# Main.net
KiCad netlist of a schematic drawn in EAGLE
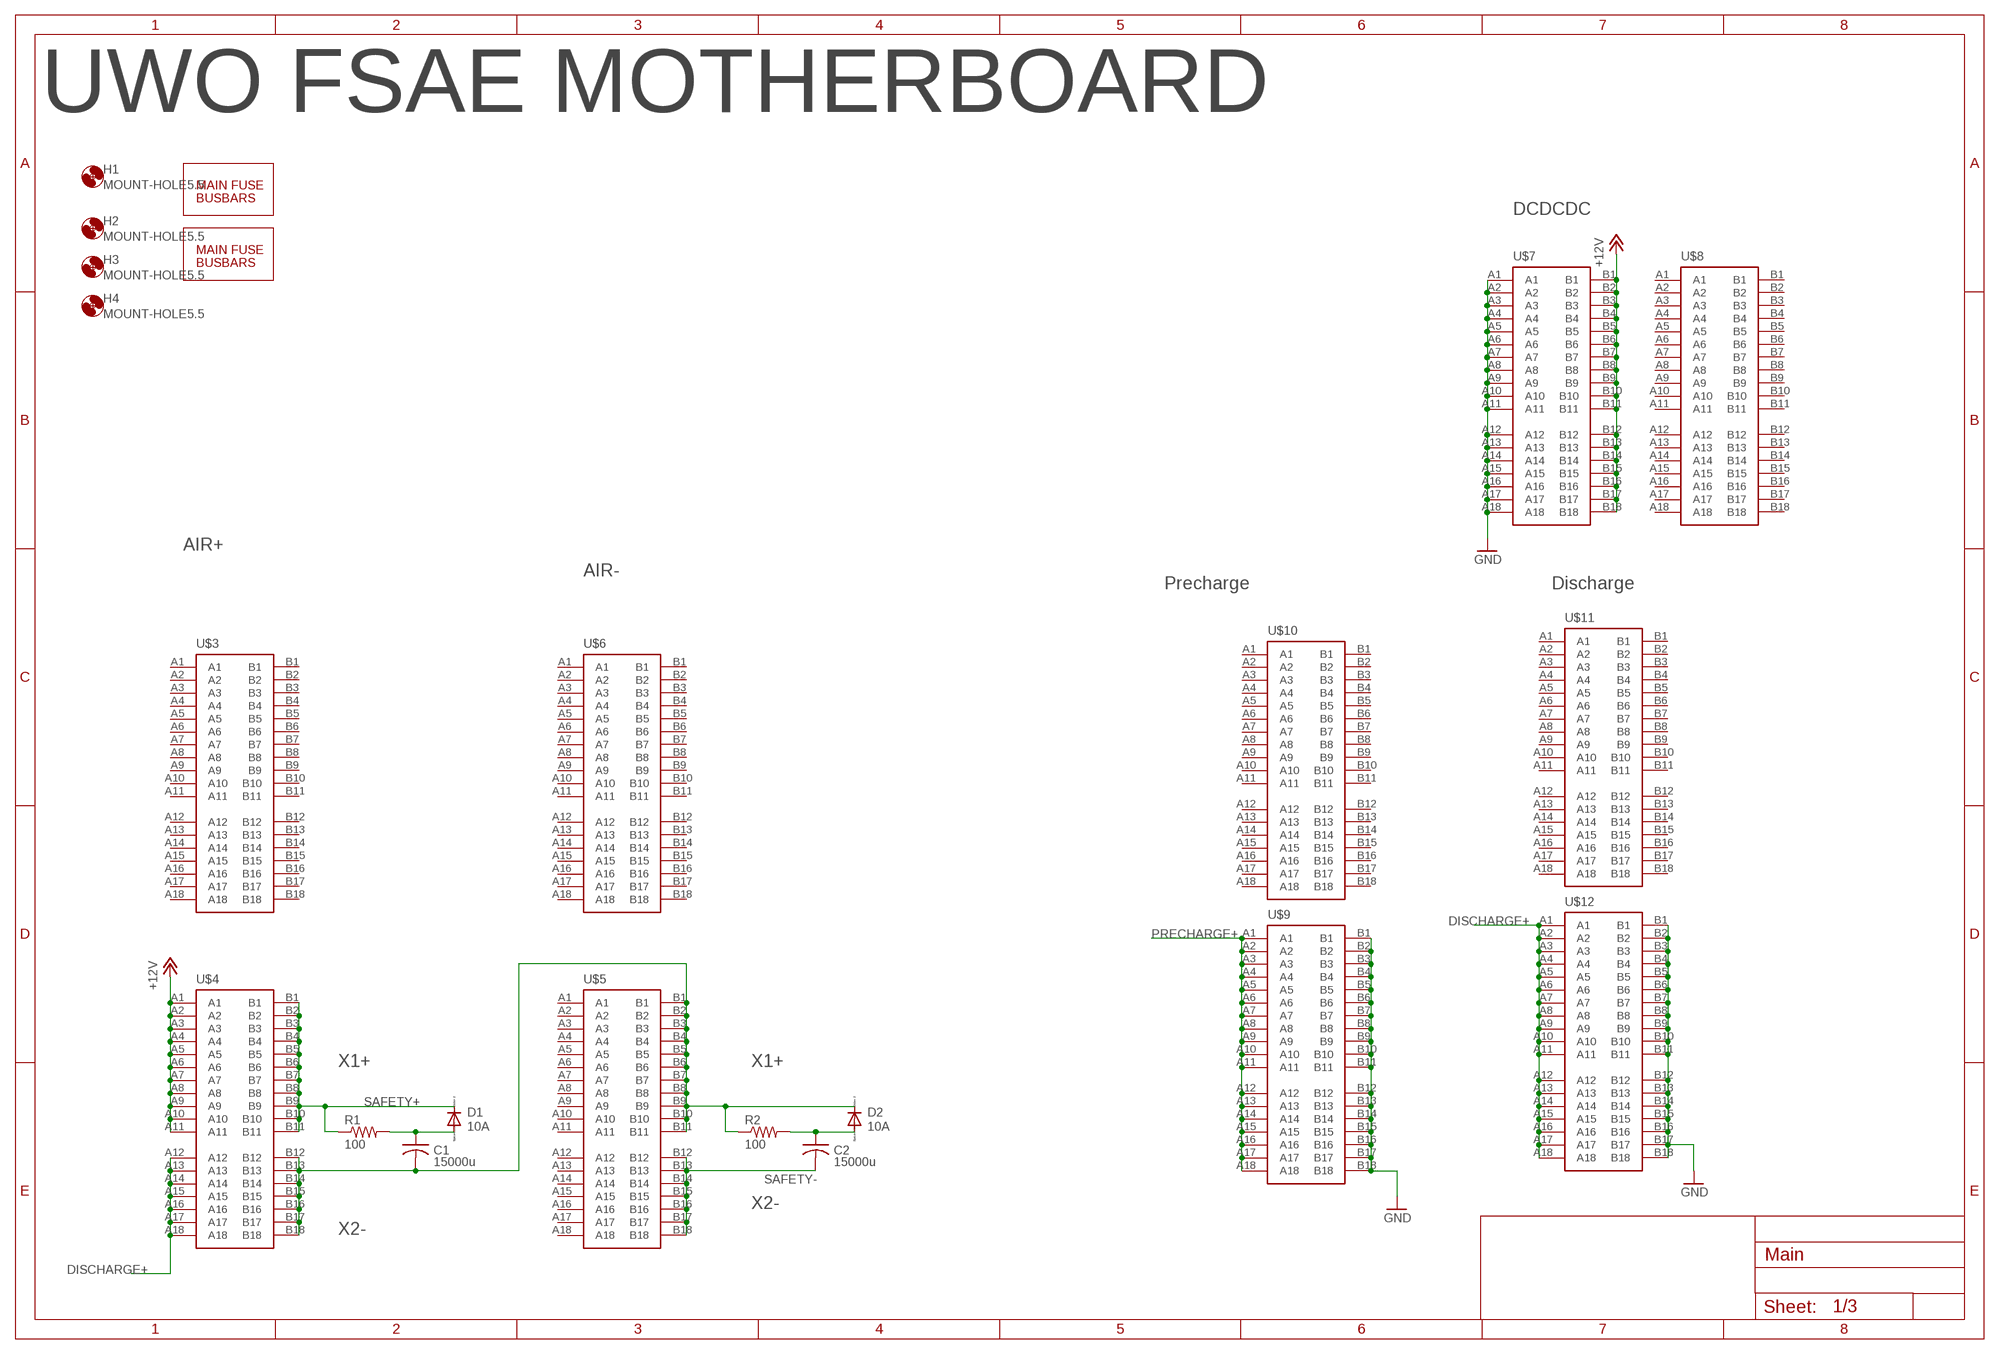
[diagram p0: schematic, sheet 1]
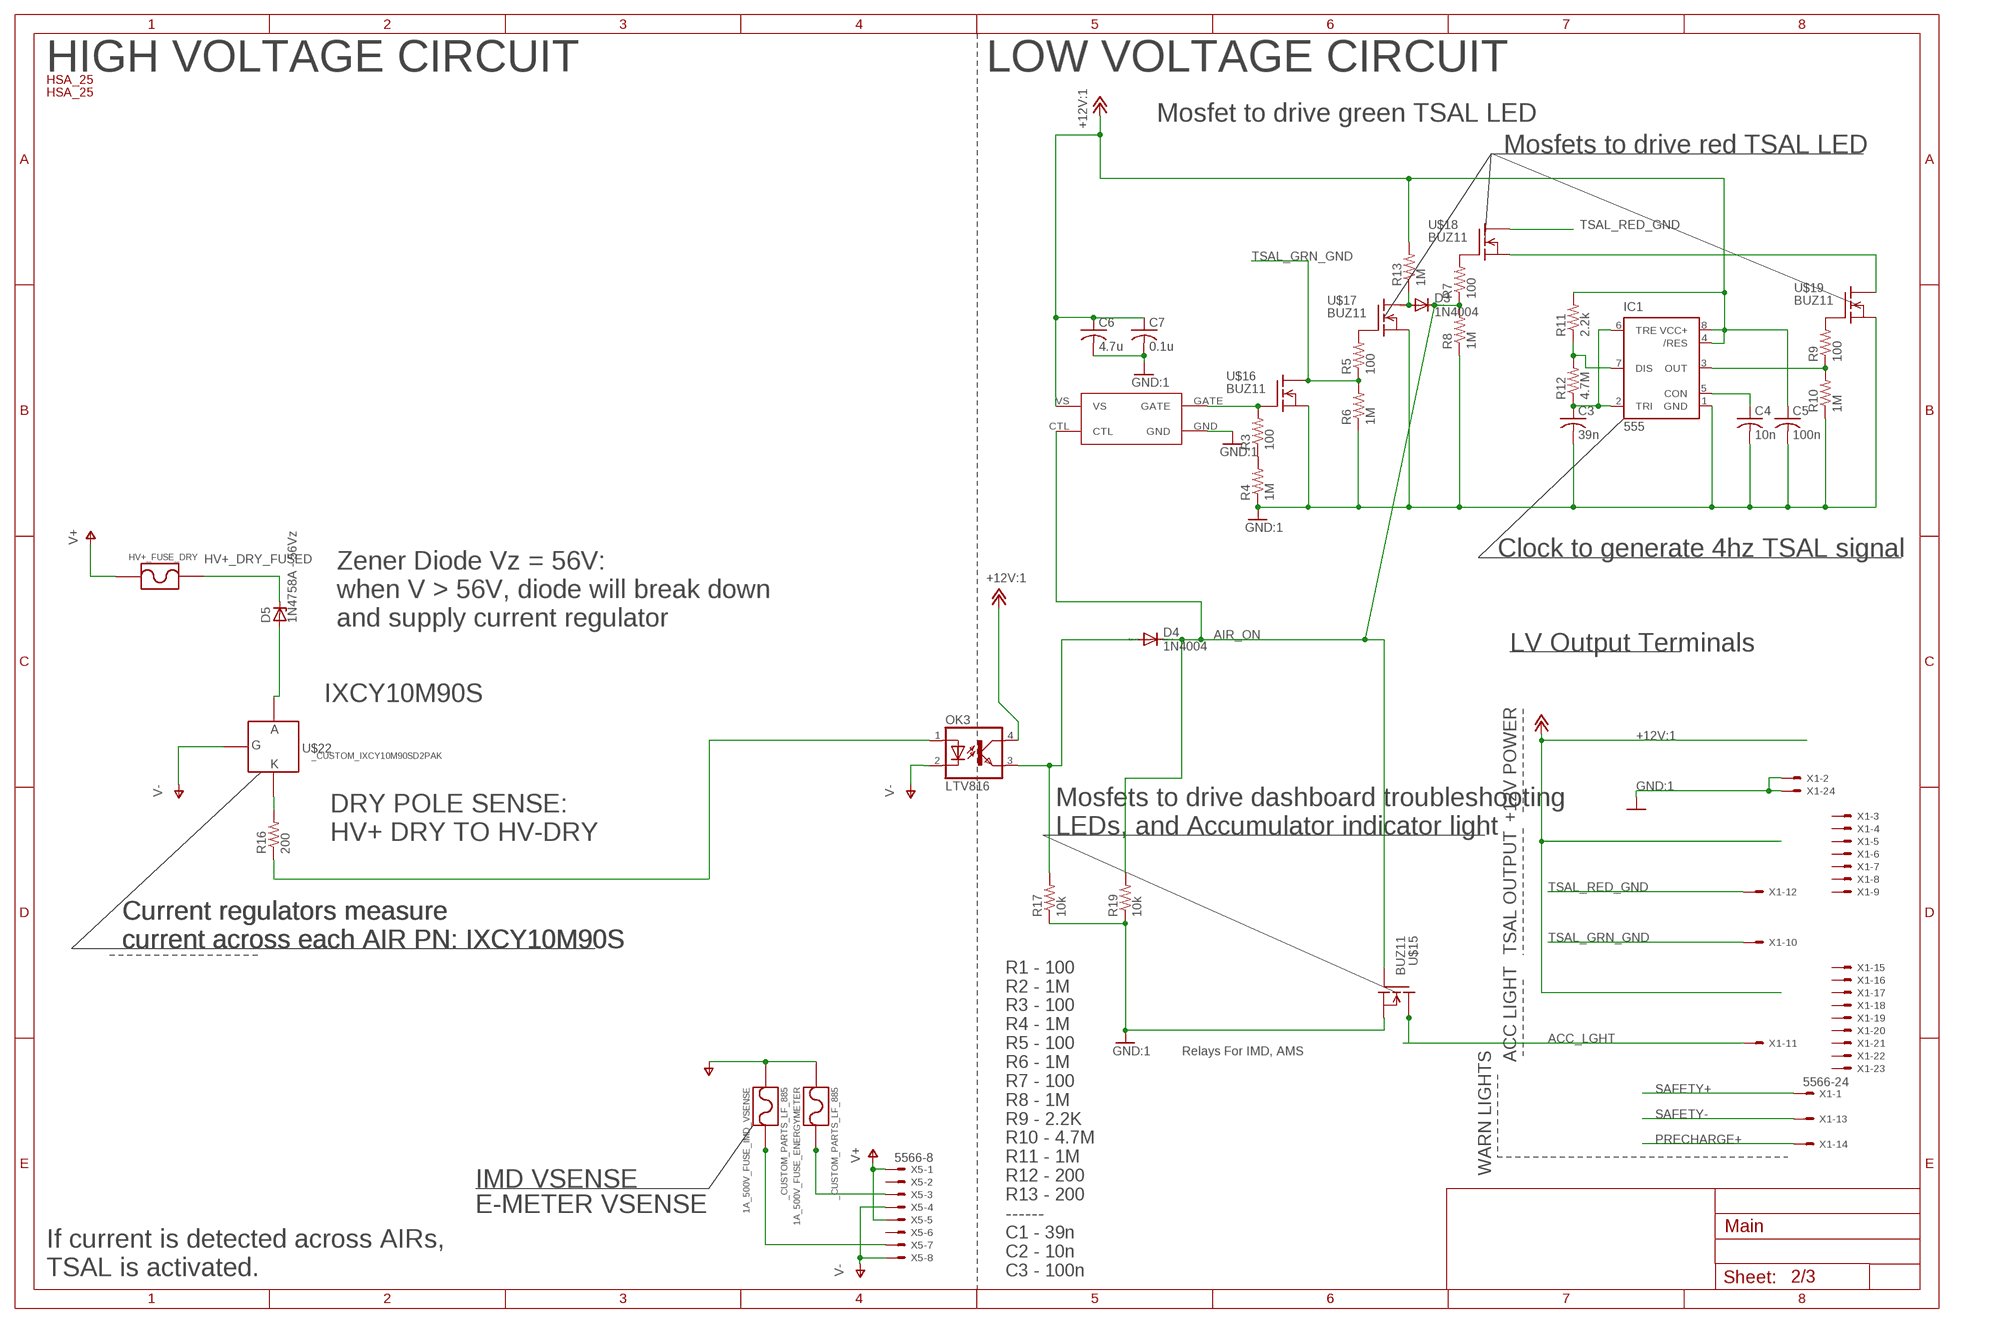
[diagram p1: schematic, sheet 2]
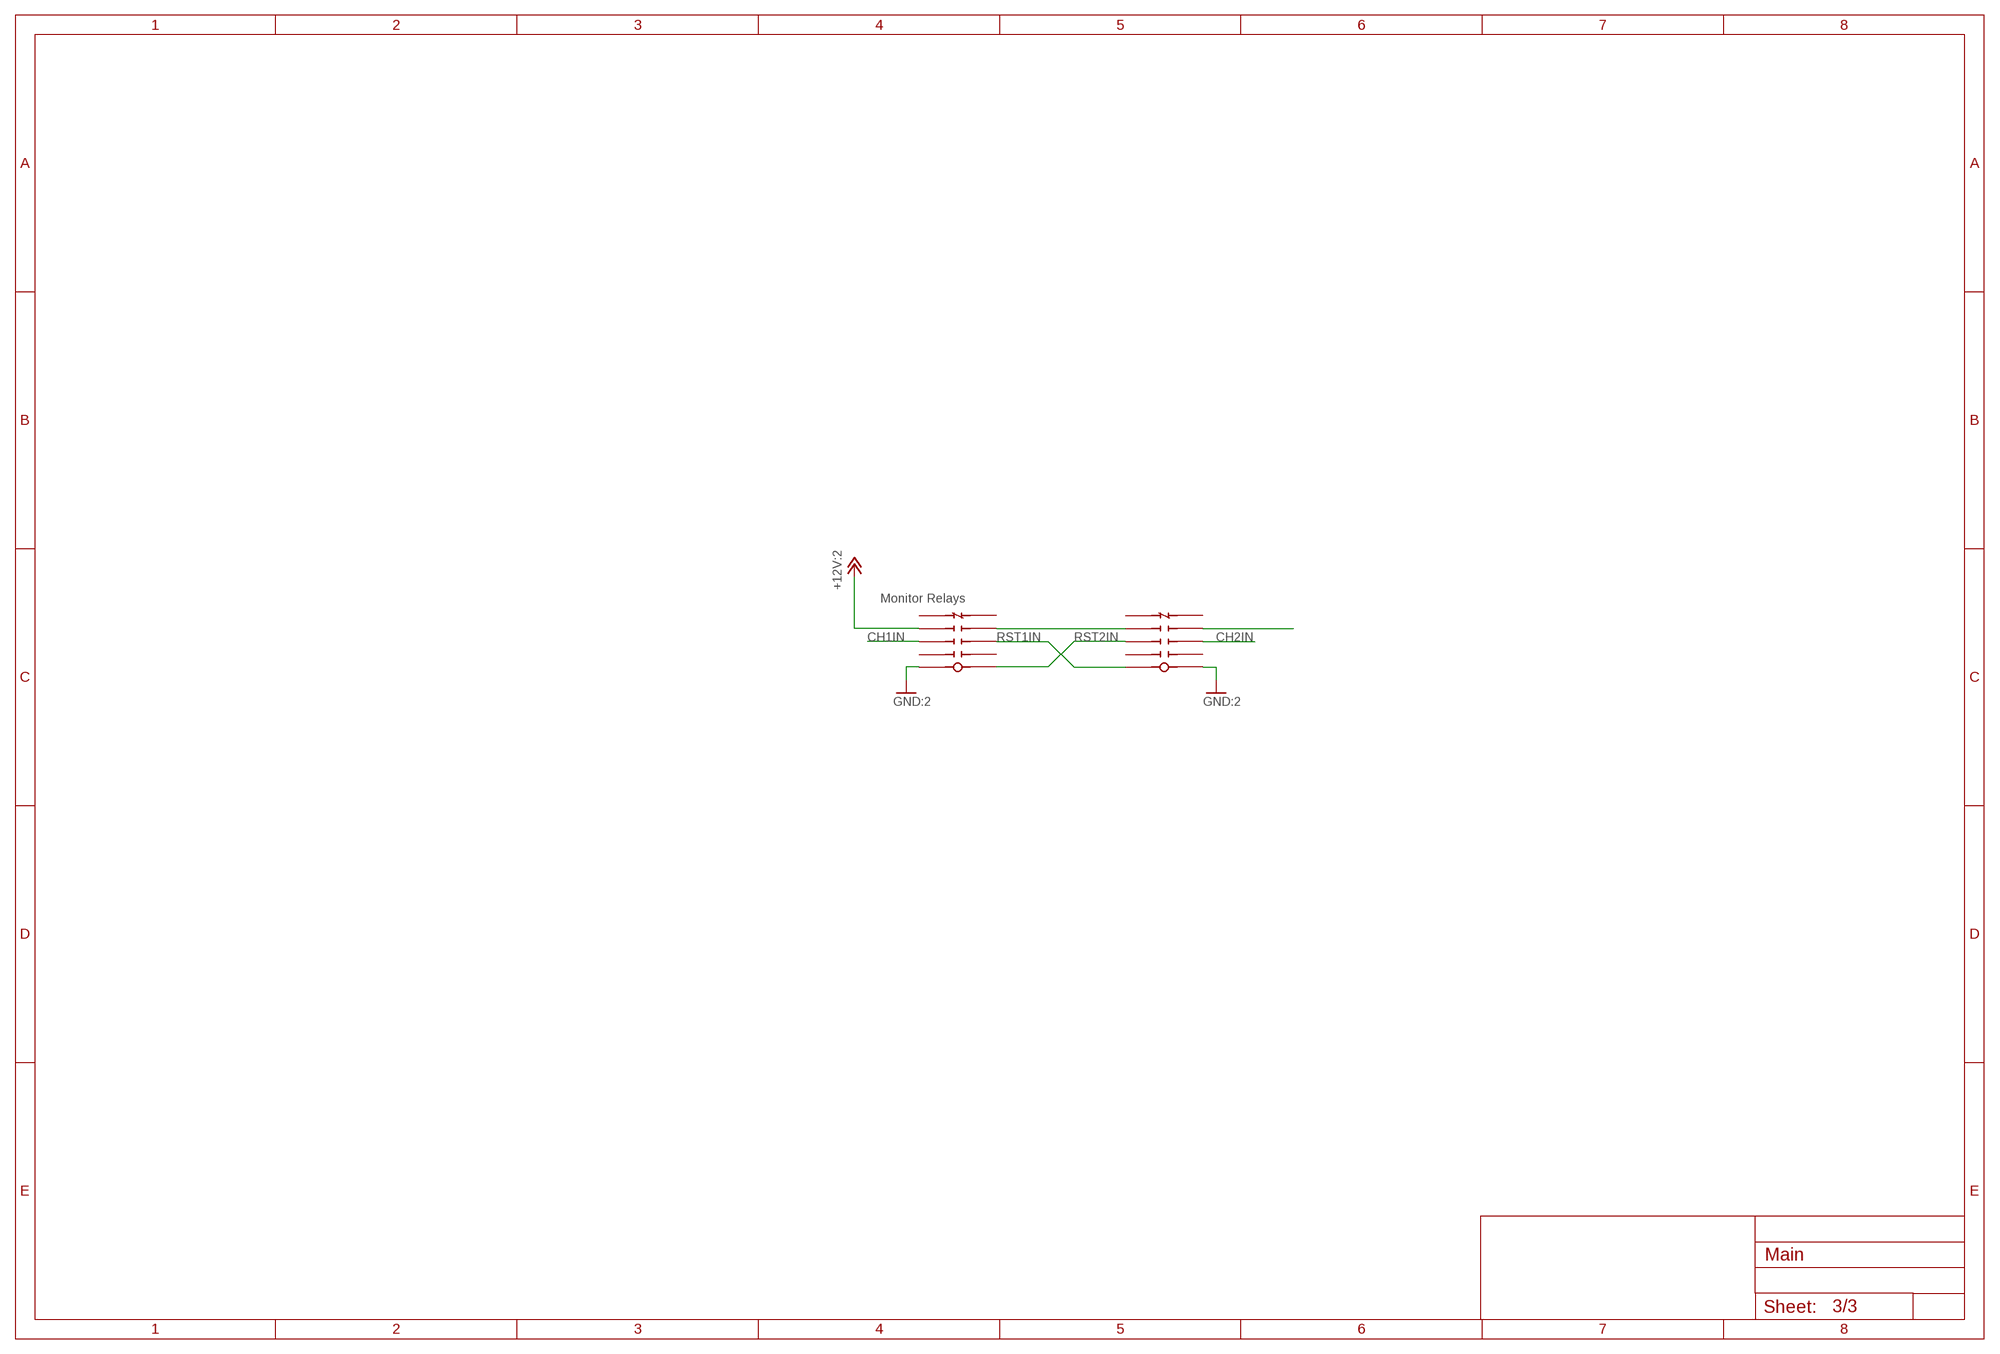
[diagram p2: schematic, sheet 3]

(export (version "E")
  (design (tool "Eeschema 10.0.6"))
  (components
    (comp (ref "1A_500V_FUSE_ENERGYMETER")
      (value "_CUSTOM_PARTS_LF_885")
      (footprint "eagle-import:_CUSTOM_PARTS_LF_885")
      (libsource (lib "eagle-import") (part "_CUSTOM_PARTS_LF_885"))
    )
    (comp (ref "1A_500V_FUSE_IMD_VSENSE")
      (value "_CUSTOM_PARTS_LF_885")
      (footprint "eagle-import:_CUSTOM_PARTS_LF_885")
      (libsource (lib "eagle-import") (part "_CUSTOM_PARTS_LF_885"))
    )
    (comp (ref "C3")
      (value "39n")
      (footprint "eagle-import:C0805")
      (libsource (lib "eagle-import") (part "C-USC0805"))
    )
    (comp (ref "C4")
      (value "10n")
      (footprint "eagle-import:C0805")
      (libsource (lib "eagle-import") (part "C-USC0805"))
    )
    (comp (ref "C5")
      (value "100n")
      (footprint "eagle-import:C0805")
      (libsource (lib "eagle-import") (part "C-USC0805"))
    )
    (comp (ref "C6")
      (value "4.7u")
      (footprint "eagle-import:C0805")
      (libsource (lib "eagle-import") (part "C-USC0805"))
    )
    (comp (ref "C7")
      (value "0.1u")
      (footprint "eagle-import:C0805")
      (libsource (lib "eagle-import") (part "C-USC0805"))
    )
    (comp (ref "D3")
      (value "1N4004")
      (footprint "eagle-import:DO41-10")
      (libsource (lib "eagle-import") (part "1N4004"))
    )
    (comp (ref "D4")
      (value "1N4004")
      (footprint "eagle-import:DO41-10")
      (libsource (lib "eagle-import") (part "1N4004"))
    )
    (comp (ref "D5")
      (value "1N4758A - 56Vz")
      (footprint "eagle-import:ZDIO12.5")
      (libsource (lib "eagle-import") (part "ZENER-DIODEZD-12.5"))
    )
    (comp (ref "HV+_FUSE_DRY")
      (value "_CUSTOM_PARTS_LF_885")
      (footprint "eagle-import:_CUSTOM_PARTS_LF_885")
      (libsource (lib "eagle-import") (part "_CUSTOM_PARTS_LF_885"))
    )
    (comp (ref "IC1")
      (value "555")
      (footprint "eagle-import:DIP08")
      (libsource (lib "eagle-import") (part "555P"))
    )
    (comp (ref "OK3")
      (value "LTV816")
      (footprint "eagle-import:DIL04")
      (libsource (lib "eagle-import") (part "LTV816"))
    )
    (comp (ref "R3")
      (value "100")
      (footprint "eagle-import:R0805_1")
      (libsource (lib "eagle-import") (part "R-US_?{colon}1R0805"))
    )
    (comp (ref "R4")
      (value "1M")
      (footprint "eagle-import:R0805_1")
      (libsource (lib "eagle-import") (part "R-US_?{colon}1R0805"))
    )
    (comp (ref "R5")
      (value "100")
      (footprint "eagle-import:R0805_1")
      (libsource (lib "eagle-import") (part "R-US_?{colon}1R0805"))
    )
    (comp (ref "R6")
      (value "1M")
      (footprint "eagle-import:R0805_1")
      (libsource (lib "eagle-import") (part "R-US_?{colon}1R0805"))
    )
    (comp (ref "R7")
      (value "100")
      (footprint "eagle-import:R0805_1")
      (libsource (lib "eagle-import") (part "R-US_?{colon}1R0805"))
    )
    (comp (ref "R8")
      (value "1M")
      (footprint "eagle-import:R0805_1")
      (libsource (lib "eagle-import") (part "R-US_?{colon}1R0805"))
    )
    (comp (ref "R9")
      (value "100")
      (footprint "eagle-import:R0805_1")
      (libsource (lib "eagle-import") (part "R-US_?{colon}1R0805"))
    )
    (comp (ref "R10")
      (value "1M")
      (footprint "eagle-import:R0805_1")
      (libsource (lib "eagle-import") (part "R-US_?{colon}1R0805"))
    )
    (comp (ref "R11")
      (value "2.2k")
      (footprint "eagle-import:R0805_1")
      (libsource (lib "eagle-import") (part "R-US_?{colon}1R0805"))
    )
    (comp (ref "R12")
      (value "4.7M")
      (footprint "eagle-import:R0805_1")
      (libsource (lib "eagle-import") (part "R-US_?{colon}1R0805"))
    )
    (comp (ref "R13")
      (value "1M")
      (footprint "eagle-import:R0805_1")
      (libsource (lib "eagle-import") (part "R-US_?{colon}1R0805"))
    )
    (comp (ref "R16")
      (value "200")
      (footprint "eagle-import:R2010")
      (libsource (lib "eagle-import") (part "R-US_R2010"))
    )
    (comp (ref "R17")
      (value "10k")
      (footprint "eagle-import:R0805_1")
      (libsource (lib "eagle-import") (part "R-US_?{colon}1R0805"))
    )
    (comp (ref "R19")
      (value "10k")
      (footprint "eagle-import:R0805_1")
      (libsource (lib "eagle-import") (part "R-US_?{colon}1R0805"))
    )
    (comp (ref "U$15")
      (value "BUZ11")
      (footprint "eagle-import:TO220")
      (libsource (lib "eagle-import") (part "BUZ11"))
    )
    (comp (ref "U$16")
      (value "BUZ11")
      (footprint "eagle-import:TO220")
      (libsource (lib "eagle-import") (part "BUZ11"))
    )
    (comp (ref "U$17")
      (value "BUZ11")
      (footprint "eagle-import:TO220")
      (libsource (lib "eagle-import") (part "BUZ11"))
    )
    (comp (ref "U$18")
      (value "BUZ11")
      (footprint "eagle-import:TO220")
      (libsource (lib "eagle-import") (part "BUZ11"))
    )
    (comp (ref "U$19")
      (value "BUZ11")
      (footprint "eagle-import:TO220")
      (libsource (lib "eagle-import") (part "BUZ11"))
    )
    (comp (ref "U$22")
      (value "_CUSTOM_IXCY10M90SD2PAK")
      (footprint "eagle-import:TO228P991X238-3")
      (libsource (lib "eagle-import") (part "_CUSTOM_IXCY10M90SD2PAK"))
    )
    (comp (ref "U$23")
      (value "MIC4417")
      (footprint "eagle-import:PDM_2019_REVB_MIC4416YM4-TR")
      (libsource (lib "eagle-import") (part "MIC4417"))
    )
    (comp (ref "U$24")
      (value "HSA25")
      (footprint "eagle-import:HSA_25_FOOT")
      (libsource (lib "eagle-import") (part "HSA25"))
    )
    (comp (ref "U$25")
      (value "HSA25")
      (footprint "eagle-import:HSA_25_FOOT")
      (libsource (lib "eagle-import") (part "HSA25"))
    )
    (comp (ref "X1")
      (value "5566-24")
      (footprint "eagle-import:5566-24")
      (fields (field (name "MF") "MOLEX"))
      (libsource (lib "eagle-import") (part "5566-24"))
    )
    (comp (ref "X5")
      (value "5566-8")
      (footprint "eagle-import:5566-8")
      (fields (field (name "MF") "MOLEX"))
      (libsource (lib "eagle-import") (part "5566-8"))
    )
    (comp (ref "C1")
      (value "15000u")
      (footprint "eagle-import:CAPPRD750W65D1800H3700B")
      (libsource (lib "eagle-import") (part "AIR_HOLDUP_CAP"))
    )
    (comp (ref "C2")
      (value "15000u")
      (footprint "eagle-import:CAPPRD750W65D1800H3700B")
      (libsource (lib "eagle-import") (part "AIR_HOLDUP_CAP"))
    )
    (comp (ref "D1")
      (value "10A")
      (footprint "eagle-import:DIOAD1570W120L850D500B")
      (libsource (lib "eagle-import") (part "AIR_HOLDUP_DIODE"))
    )
    (comp (ref "D2")
      (value "10A")
      (footprint "eagle-import:DIOAD1570W120L850D500B")
      (libsource (lib "eagle-import") (part "AIR_HOLDUP_DIODE"))
    )
    (comp (ref "H1")
      (value "MOUNT-HOLE5.5")
      (footprint "eagle-import:5,5")
      (libsource (lib "eagle-import") (part "MOUNT-HOLE5.5"))
    )
    (comp (ref "H2")
      (value "MOUNT-HOLE5.5")
      (footprint "eagle-import:5,5")
      (libsource (lib "eagle-import") (part "MOUNT-HOLE5.5"))
    )
    (comp (ref "H3")
      (value "MOUNT-HOLE5.5")
      (footprint "eagle-import:5,5")
      (libsource (lib "eagle-import") (part "MOUNT-HOLE5.5"))
    )
    (comp (ref "H4")
      (value "MOUNT-HOLE5.5")
      (footprint "eagle-import:5,5")
      (libsource (lib "eagle-import") (part "MOUNT-HOLE5.5"))
    )
    (comp (ref "R1")
      (value "100")
      (footprint "eagle-import:RESAD976W63L650D250B")
      (libsource (lib "eagle-import") (part "AIR_HOLDUP_RESISTOR"))
    )
    (comp (ref "R2")
      (value "100")
      (footprint "eagle-import:RESAD976W63L650D250B")
      (libsource (lib "eagle-import") (part "AIR_HOLDUP_RESISTOR"))
    )
    (comp (ref "U$1")
      (value "FUSE_HOLDER")
      (footprint "eagle-import:FUSE_HOLDER")
      (libsource (lib "eagle-import") (part "FUSE_HOLDER"))
    )
    (comp (ref "U$2")
      (value "FUSE_HOLDER")
      (footprint "eagle-import:FUSE_HOLDER")
      (libsource (lib "eagle-import") (part "FUSE_HOLDER"))
    )
    (comp (ref "U$3")
      (value "PCIE-36-CONN")
      (footprint "eagle-import:PCI-E-36-CONN")
      (libsource (lib "eagle-import") (part "PCIE-36-CONN"))
    )
    (comp (ref "U$4")
      (value "PCIE-36-CONN")
      (footprint "eagle-import:PCI-E-36-CONN")
      (libsource (lib "eagle-import") (part "PCIE-36-CONN"))
    )
    (comp (ref "U$5")
      (value "PCIE-36-CONN")
      (footprint "eagle-import:PCI-E-36-CONN")
      (libsource (lib "eagle-import") (part "PCIE-36-CONN"))
    )
    (comp (ref "U$6")
      (value "PCIE-36-CONN")
      (footprint "eagle-import:PCI-E-36-CONN")
      (libsource (lib "eagle-import") (part "PCIE-36-CONN"))
    )
    (comp (ref "U$7")
      (value "PCIE-36-CONN")
      (footprint "eagle-import:PCI-E-36-CONN")
      (libsource (lib "eagle-import") (part "PCIE-36-CONN"))
    )
    (comp (ref "U$8")
      (value "PCIE-36-CONN")
      (footprint "eagle-import:PCI-E-36-CONN")
      (libsource (lib "eagle-import") (part "PCIE-36-CONN"))
    )
    (comp (ref "U$9")
      (value "PCIE-36-CONN")
      (footprint "eagle-import:PCI-E-36-CONN")
      (libsource (lib "eagle-import") (part "PCIE-36-CONN"))
    )
    (comp (ref "U$10")
      (value "PCIE-36-CONN")
      (footprint "eagle-import:PCI-E-36-CONN")
      (libsource (lib "eagle-import") (part "PCIE-36-CONN"))
    )
    (comp (ref "U$11")
      (value "PCIE-36-CONN")
      (footprint "eagle-import:PCI-E-36-CONN")
      (libsource (lib "eagle-import") (part "PCIE-36-CONN"))
    )
    (comp (ref "U$12")
      (value "PCIE-36-CONN")
      (footprint "eagle-import:PCI-E-36-CONN")
      (libsource (lib "eagle-import") (part "PCIE-36-CONN"))
    )
    (comp (ref "U$13")
      (value "SR4M4012_TE")
      (footprint "eagle-import:SR4M4012_FOOT")
      (libsource (lib "eagle-import") (part "SR4M4012_TE"))
    )
    (comp (ref "U$14")
      (value "SR4M4012_TE")
      (footprint "eagle-import:SR4M4012_FOOT")
      (libsource (lib "eagle-import") (part "SR4M4012_TE"))
    )
  )
  (nets
    (net (code "1") (name "+12V") (class "Default")
      (node (ref "C5") (pin "1") (pinfunction "1_1") (pintype "passive"))
      (node (ref "C6") (pin "1") (pinfunction "1_1") (pintype "passive"))
      (node (ref "C7") (pin "1") (pinfunction "1_1") (pintype "passive"))
      (node (ref "IC1") (pin "4") (pinfunction "/RES_4") (pintype "input"))
      (node (ref "IC1") (pin "8") (pinfunction "VCC+_8") (pintype "power_in"))
      (node (ref "OK3") (pin "4") (pinfunction "COL_4") (pintype "passive"))
      (node (ref "R11") (pin "2") (pinfunction "2_2") (pintype "passive"))
      (node (ref "R13") (pin "2") (pinfunction "2_2") (pintype "passive"))
      (node (ref "U$13") (pin "NOA3") (pinfunction "NOA3_NOA3") (pintype "bidirectional"))
      (node (ref "U$23") (pin "VS") (pinfunction "VS_VS") (pintype "bidirectional"))
      (node (ref "U$4") (pin "A1") (pinfunction "A1_A1") (pintype "passive"))
      (node (ref "U$4") (pin "A10") (pinfunction "A10_A10") (pintype "passive"))
      (node (ref "U$4") (pin "A11") (pinfunction "A11_A11") (pintype "passive"))
      (node (ref "U$4") (pin "A2") (pinfunction "A2_A2") (pintype "passive"))
      (node (ref "U$4") (pin "A3") (pinfunction "A3_A3") (pintype "passive"))
      (node (ref "U$4") (pin "A4") (pinfunction "A4_A4") (pintype "passive"))
      (node (ref "U$4") (pin "A5") (pinfunction "A5_A5") (pintype "passive"))
      (node (ref "U$4") (pin "A6") (pinfunction "A6_A6") (pintype "passive"))
      (node (ref "U$4") (pin "A7") (pinfunction "A7_A7") (pintype "passive"))
      (node (ref "U$4") (pin "A8") (pinfunction "A8_A8") (pintype "passive"))
      (node (ref "U$4") (pin "A9") (pinfunction "A9_A9") (pintype "passive"))
      (node (ref "U$7") (pin "B1") (pinfunction "B1_B1") (pintype "passive"))
      (node (ref "U$7") (pin "B10") (pinfunction "B10_B10") (pintype "passive"))
      (node (ref "U$7") (pin "B11") (pinfunction "B11_B11") (pintype "passive"))
      (node (ref "U$7") (pin "B12") (pinfunction "B12_B12") (pintype "passive"))
      (node (ref "U$7") (pin "B13") (pinfunction "B13_B13") (pintype "passive"))
      (node (ref "U$7") (pin "B14") (pinfunction "B14_B14") (pintype "passive"))
      (node (ref "U$7") (pin "B15") (pinfunction "B15_B15") (pintype "passive"))
      (node (ref "U$7") (pin "B16") (pinfunction "B16_B16") (pintype "passive"))
      (node (ref "U$7") (pin "B17") (pinfunction "B17_B17") (pintype "passive"))
      (node (ref "U$7") (pin "B18") (pinfunction "B18_B18") (pintype "passive"))
      (node (ref "U$7") (pin "B2") (pinfunction "B2_B2") (pintype "passive"))
      (node (ref "U$7") (pin "B3") (pinfunction "B3_B3") (pintype "passive"))
      (node (ref "U$7") (pin "B4") (pinfunction "B4_B4") (pintype "passive"))
      (node (ref "U$7") (pin "B5") (pinfunction "B5_B5") (pintype "passive"))
      (node (ref "U$7") (pin "B6") (pinfunction "B6_B6") (pintype "passive"))
      (node (ref "U$7") (pin "B7") (pinfunction "B7_B7") (pintype "passive"))
      (node (ref "U$7") (pin "B8") (pinfunction "B8_B8") (pintype "passive"))
      (node (ref "U$7") (pin "B9") (pinfunction "B9_B9") (pintype "passive"))
    )
    (net (code "2") (name "ACC_LGHT") (class "Default")
      (node (ref "U$15") (pin "2") (pinfunction "D_2") (pintype "passive"))
      (node (ref "X1") (pin "11") (pinfunction "S_11") (pintype "passive"))
    )
    (net (code "3") (name "AIR_ON") (class "Default")
      (node (ref "D3") (pin "C") (pinfunction "C_C") (pintype "passive"))
      (node (ref "D4") (pin "C") (pinfunction "C_C") (pintype "passive"))
      (node (ref "R19") (pin "2") (pinfunction "2_2") (pintype "passive"))
      (node (ref "R7") (pin "1") (pinfunction "1_1") (pintype "passive"))
      (node (ref "R8") (pin "2") (pinfunction "2_2") (pintype "passive"))
      (node (ref "U$15") (pin "1") (pinfunction "G_1") (pintype "passive"))
      (node (ref "U$23") (pin "CTL") (pinfunction "CTL_CTL") (pintype "bidirectional"))
    )
    (net (code "4") (name "CH1IN") (class "Default")
      (node (ref "U$13") (pin "NOA2") (pinfunction "NOA2_NOA2") (pintype "bidirectional"))
    )
    (net (code "5") (name "CH2IN") (class "Default")
      (node (ref "U$14") (pin "NOB2") (pinfunction "NOB2_NOB2") (pintype "bidirectional"))
    )
    (net (code "6") (name "DISCHARGE+") (class "Default")
      (node (ref "U$12") (pin "A1") (pinfunction "A1_A1") (pintype "passive"))
      (node (ref "U$12") (pin "A10") (pinfunction "A10_A10") (pintype "passive"))
      (node (ref "U$12") (pin "A11") (pinfunction "A11_A11") (pintype "passive"))
      (node (ref "U$12") (pin "A12") (pinfunction "A12_A12") (pintype "passive"))
      (node (ref "U$12") (pin "A13") (pinfunction "A13_A13") (pintype "passive"))
      (node (ref "U$12") (pin "A14") (pinfunction "A14_A14") (pintype "passive"))
      (node (ref "U$12") (pin "A15") (pinfunction "A15_A15") (pintype "passive"))
      (node (ref "U$12") (pin "A16") (pinfunction "A16_A16") (pintype "passive"))
      (node (ref "U$12") (pin "A17") (pinfunction "A17_A17") (pintype "passive"))
      (node (ref "U$12") (pin "A18") (pinfunction "A18_A18") (pintype "passive"))
      (node (ref "U$12") (pin "A2") (pinfunction "A2_A2") (pintype "passive"))
      (node (ref "U$12") (pin "A3") (pinfunction "A3_A3") (pintype "passive"))
      (node (ref "U$12") (pin "A4") (pinfunction "A4_A4") (pintype "passive"))
      (node (ref "U$12") (pin "A5") (pinfunction "A5_A5") (pintype "passive"))
      (node (ref "U$12") (pin "A6") (pinfunction "A6_A6") (pintype "passive"))
      (node (ref "U$12") (pin "A7") (pinfunction "A7_A7") (pintype "passive"))
      (node (ref "U$12") (pin "A8") (pinfunction "A8_A8") (pintype "passive"))
      (node (ref "U$12") (pin "A9") (pinfunction "A9_A9") (pintype "passive"))
      (node (ref "U$4") (pin "A12") (pinfunction "A12_A12") (pintype "passive"))
      (node (ref "U$4") (pin "A13") (pinfunction "A13_A13") (pintype "passive"))
      (node (ref "U$4") (pin "A14") (pinfunction "A14_A14") (pintype "passive"))
      (node (ref "U$4") (pin "A15") (pinfunction "A15_A15") (pintype "passive"))
      (node (ref "U$4") (pin "A16") (pinfunction "A16_A16") (pintype "passive"))
      (node (ref "U$4") (pin "A17") (pinfunction "A17_A17") (pintype "passive"))
      (node (ref "U$4") (pin "A18") (pinfunction "A18_A18") (pintype "passive"))
    )
    (net (code "7") (name "GND") (class "Default")
      (node (ref "C3") (pin "2") (pinfunction "2_2") (pintype "passive"))
      (node (ref "C4") (pin "2") (pinfunction "2_2") (pintype "passive"))
      (node (ref "C5") (pin "2") (pinfunction "2_2") (pintype "passive"))
      (node (ref "C6") (pin "2") (pinfunction "2_2") (pintype "passive"))
      (node (ref "C7") (pin "2") (pinfunction "2_2") (pintype "passive"))
      (node (ref "IC1") (pin "1") (pinfunction "GND_1") (pintype "power_in"))
      (node (ref "R10") (pin "1") (pinfunction "1_1") (pintype "passive"))
      (node (ref "R17") (pin "1") (pinfunction "1_1") (pintype "passive"))
      (node (ref "R19") (pin "1") (pinfunction "1_1") (pintype "passive"))
      (node (ref "R4") (pin "1") (pinfunction "1_1") (pintype "passive"))
      (node (ref "R6") (pin "1") (pinfunction "1_1") (pintype "passive"))
      (node (ref "R8") (pin "1") (pinfunction "1_1") (pintype "passive"))
      (node (ref "U$12") (pin "B1") (pinfunction "B1_B1") (pintype "passive"))
      (node (ref "U$12") (pin "B10") (pinfunction "B10_B10") (pintype "passive"))
      (node (ref "U$12") (pin "B11") (pinfunction "B11_B11") (pintype "passive"))
      (node (ref "U$12") (pin "B12") (pinfunction "B12_B12") (pintype "passive"))
      (node (ref "U$12") (pin "B13") (pinfunction "B13_B13") (pintype "passive"))
      (node (ref "U$12") (pin "B14") (pinfunction "B14_B14") (pintype "passive"))
      (node (ref "U$12") (pin "B15") (pinfunction "B15_B15") (pintype "passive"))
      (node (ref "U$12") (pin "B16") (pinfunction "B16_B16") (pintype "passive"))
      (node (ref "U$12") (pin "B17") (pinfunction "B17_B17") (pintype "passive"))
      (node (ref "U$12") (pin "B18") (pinfunction "B18_B18") (pintype "passive"))
      (node (ref "U$12") (pin "B2") (pinfunction "B2_B2") (pintype "passive"))
      (node (ref "U$12") (pin "B3") (pinfunction "B3_B3") (pintype "passive"))
      (node (ref "U$12") (pin "B4") (pinfunction "B4_B4") (pintype "passive"))
      (node (ref "U$12") (pin "B5") (pinfunction "B5_B5") (pintype "passive"))
      (node (ref "U$12") (pin "B6") (pinfunction "B6_B6") (pintype "passive"))
      (node (ref "U$12") (pin "B7") (pinfunction "B7_B7") (pintype "passive"))
      (node (ref "U$12") (pin "B8") (pinfunction "B8_B8") (pintype "passive"))
      (node (ref "U$12") (pin "B9") (pinfunction "B9_B9") (pintype "passive"))
      (node (ref "U$13") (pin "COIL+") (pinfunction "COIL+_COIL+") (pintype "bidirectional"))
      (node (ref "U$14") (pin "COIL-") (pinfunction "COIL-_COIL-") (pintype "bidirectional"))
      (node (ref "U$15") (pin "3") (pinfunction "S_3") (pintype "passive"))
      (node (ref "U$16") (pin "3") (pinfunction "S_3") (pintype "passive"))
      (node (ref "U$17") (pin "3") (pinfunction "S_3") (pintype "passive"))
      (node (ref "U$19") (pin "3") (pinfunction "S_3") (pintype "passive"))
      (node (ref "U$23") (pin "GND") (pinfunction "GND_GND") (pintype "bidirectional"))
      (node (ref "U$7") (pin "A1") (pinfunction "A1_A1") (pintype "passive"))
      (node (ref "U$7") (pin "A10") (pinfunction "A10_A10") (pintype "passive"))
      (node (ref "U$7") (pin "A11") (pinfunction "A11_A11") (pintype "passive"))
      (node (ref "U$7") (pin "A12") (pinfunction "A12_A12") (pintype "passive"))
      (node (ref "U$7") (pin "A13") (pinfunction "A13_A13") (pintype "passive"))
      (node (ref "U$7") (pin "A14") (pinfunction "A14_A14") (pintype "passive"))
      (node (ref "U$7") (pin "A15") (pinfunction "A15_A15") (pintype "passive"))
      (node (ref "U$7") (pin "A16") (pinfunction "A16_A16") (pintype "passive"))
      (node (ref "U$7") (pin "A17") (pinfunction "A17_A17") (pintype "passive"))
      (node (ref "U$7") (pin "A18") (pinfunction "A18_A18") (pintype "passive"))
      (node (ref "U$7") (pin "A2") (pinfunction "A2_A2") (pintype "passive"))
      (node (ref "U$7") (pin "A3") (pinfunction "A3_A3") (pintype "passive"))
      (node (ref "U$7") (pin "A4") (pinfunction "A4_A4") (pintype "passive"))
      (node (ref "U$7") (pin "A5") (pinfunction "A5_A5") (pintype "passive"))
      (node (ref "U$7") (pin "A6") (pinfunction "A6_A6") (pintype "passive"))
      (node (ref "U$7") (pin "A7") (pinfunction "A7_A7") (pintype "passive"))
      (node (ref "U$7") (pin "A8") (pinfunction "A8_A8") (pintype "passive"))
      (node (ref "U$7") (pin "A9") (pinfunction "A9_A9") (pintype "passive"))
      (node (ref "U$9") (pin "B1") (pinfunction "B1_B1") (pintype "passive"))
      (node (ref "U$9") (pin "B10") (pinfunction "B10_B10") (pintype "passive"))
      (node (ref "U$9") (pin "B11") (pinfunction "B11_B11") (pintype "passive"))
      (node (ref "U$9") (pin "B12") (pinfunction "B12_B12") (pintype "passive"))
      (node (ref "U$9") (pin "B13") (pinfunction "B13_B13") (pintype "passive"))
      (node (ref "U$9") (pin "B14") (pinfunction "B14_B14") (pintype "passive"))
      (node (ref "U$9") (pin "B15") (pinfunction "B15_B15") (pintype "passive"))
      (node (ref "U$9") (pin "B16") (pinfunction "B16_B16") (pintype "passive"))
      (node (ref "U$9") (pin "B17") (pinfunction "B17_B17") (pintype "passive"))
      (node (ref "U$9") (pin "B18") (pinfunction "B18_B18") (pintype "passive"))
      (node (ref "U$9") (pin "B2") (pinfunction "B2_B2") (pintype "passive"))
      (node (ref "U$9") (pin "B3") (pinfunction "B3_B3") (pintype "passive"))
      (node (ref "U$9") (pin "B4") (pinfunction "B4_B4") (pintype "passive"))
      (node (ref "U$9") (pin "B5") (pinfunction "B5_B5") (pintype "passive"))
      (node (ref "U$9") (pin "B6") (pinfunction "B6_B6") (pintype "passive"))
      (node (ref "U$9") (pin "B7") (pinfunction "B7_B7") (pintype "passive"))
      (node (ref "U$9") (pin "B8") (pinfunction "B8_B8") (pintype "passive"))
      (node (ref "U$9") (pin "B9") (pinfunction "B9_B9") (pintype "passive"))
      (node (ref "X1") (pin "2") (pinfunction "S_2") (pintype "passive"))
      (node (ref "X1") (pin "24") (pinfunction "S_24") (pintype "passive"))
    )
    (net (code "8") (name "HV+_DRY_FUSED") (class "Default")
      (node (ref "D5") (pin "C") (pinfunction "C_C") (pintype "passive"))
      (node (ref "HV+_FUSE_DRY") (pin "P$1") (pinfunction "P$1_P$1") (pintype "bidirectional"))
    )
    (net (code "9") (name "Net-(D1-A)") (class "Default")
      (node (ref "C1") (pin "1") (pinfunction "1_1") (pintype "passive"))
      (node (ref "D1") (pin "2") (pinfunction "A_2") (pintype "passive"))
      (node (ref "R1") (pin "2") (pinfunction "2_2") (pintype "passive"))
    )
    (net (code "10") (name "Net-(D2-A)") (class "Default")
      (node (ref "C2") (pin "1") (pinfunction "1_1") (pintype "passive"))
      (node (ref "D2") (pin "2") (pinfunction "A_2") (pintype "passive"))
      (node (ref "R2") (pin "2") (pinfunction "2_2") (pintype "passive"))
    )
    (net (code "11") (name "Net-(D2-C)") (class "Default")
      (node (ref "C1") (pin "2") (pinfunction "2_2") (pintype "passive"))
      (node (ref "D2") (pin "1") (pinfunction "C_1") (pintype "passive"))
      (node (ref "R2") (pin "1") (pinfunction "1_1") (pintype "passive"))
      (node (ref "U$4") (pin "B12") (pinfunction "B12_B12") (pintype "passive"))
      (node (ref "U$4") (pin "B13") (pinfunction "B13_B13") (pintype "passive"))
      (node (ref "U$4") (pin "B14") (pinfunction "B14_B14") (pintype "passive"))
      (node (ref "U$4") (pin "B15") (pinfunction "B15_B15") (pintype "passive"))
      (node (ref "U$4") (pin "B16") (pinfunction "B16_B16") (pintype "passive"))
      (node (ref "U$4") (pin "B17") (pinfunction "B17_B17") (pintype "passive"))
      (node (ref "U$4") (pin "B18") (pinfunction "B18_B18") (pintype "passive"))
      (node (ref "U$5") (pin "B1") (pinfunction "B1_B1") (pintype "passive"))
      (node (ref "U$5") (pin "B10") (pinfunction "B10_B10") (pintype "passive"))
      (node (ref "U$5") (pin "B11") (pinfunction "B11_B11") (pintype "passive"))
      (node (ref "U$5") (pin "B2") (pinfunction "B2_B2") (pintype "passive"))
      (node (ref "U$5") (pin "B3") (pinfunction "B3_B3") (pintype "passive"))
      (node (ref "U$5") (pin "B4") (pinfunction "B4_B4") (pintype "passive"))
      (node (ref "U$5") (pin "B5") (pinfunction "B5_B5") (pintype "passive"))
      (node (ref "U$5") (pin "B6") (pinfunction "B6_B6") (pintype "passive"))
      (node (ref "U$5") (pin "B7") (pinfunction "B7_B7") (pintype "passive"))
      (node (ref "U$5") (pin "B8") (pinfunction "B8_B8") (pintype "passive"))
      (node (ref "U$5") (pin "B9") (pinfunction "B9_B9") (pintype "passive"))
    )
    (net (code "12") (name "Net-(IC1-CON)") (class "Default")
      (node (ref "C4") (pin "1") (pinfunction "1_1") (pintype "passive"))
      (node (ref "IC1") (pin "5") (pinfunction "CON_5") (pintype "input"))
    )
    (net (code "13") (name "Net-(IC1-DIS)") (class "Default")
      (node (ref "IC1") (pin "7") (pinfunction "DIS_7") (pintype "input"))
      (node (ref "R11") (pin "1") (pinfunction "1_1") (pintype "passive"))
      (node (ref "R12") (pin "2") (pinfunction "2_2") (pintype "passive"))
    )
    (net (code "14") (name "Net-(IC1-OUT)") (class "Default")
      (node (ref "IC1") (pin "3") (pinfunction "OUT_3") (pintype "output"))
      (node (ref "R10") (pin "2") (pinfunction "2_2") (pintype "passive"))
      (node (ref "R9") (pin "1") (pinfunction "1_1") (pintype "passive"))
    )
    (net (code "15") (name "Net-(IC1-TRE)") (class "Default")
      (node (ref "C3") (pin "1") (pinfunction "1_1") (pintype "passive"))
      (node (ref "IC1") (pin "2") (pinfunction "TRI_2") (pintype "input"))
      (node (ref "IC1") (pin "6") (pinfunction "TRE_6") (pintype "input"))
      (node (ref "R12") (pin "1") (pinfunction "1_1") (pintype "passive"))
    )
    (net (code "16") (name "Net-(OK3-A)") (class "Default")
      (node (ref "OK3") (pin "1") (pinfunction "A_1") (pintype "passive"))
      (node (ref "R16") (pin "1") (pinfunction "1_1") (pintype "passive"))
    )
    (net (code "17") (name "Net-(OK3-EMIT)") (class "Default")
      (node (ref "D4") (pin "A") (pinfunction "A_A") (pintype "passive"))
      (node (ref "OK3") (pin "3") (pinfunction "EMIT_3") (pintype "passive"))
      (node (ref "R17") (pin "2") (pinfunction "2_2") (pintype "passive"))
    )
    (net (code "18") (name "Net-(R3-Pad1)") (class "Default")
      (node (ref "R3") (pin "1") (pinfunction "1_1") (pintype "passive"))
      (node (ref "R4") (pin "2") (pinfunction "2_2") (pintype "passive"))
    )
    (net (code "19") (name "Net-(U$13-PadNOB3)") (class "Default")
      (node (ref "U$13") (pin "NOB3") (pinfunction "NOB3_NOB3") (pintype "bidirectional"))
      (node (ref "U$14") (pin "NOA3") (pinfunction "NOA3_NOA3") (pintype "bidirectional"))
    )
    (net (code "20") (name "Net-(U$16-G)") (class "Default")
      (node (ref "R3") (pin "2") (pinfunction "2_2") (pintype "passive"))
      (node (ref "U$16") (pin "1") (pinfunction "G_1") (pintype "passive"))
      (node (ref "U$23") (pin "GATE") (pinfunction "GATE_GATE") (pintype "bidirectional"))
    )
    (net (code "21") (name "Net-(U$17-D)") (class "Default")
      (node (ref "D3") (pin "A") (pinfunction "A_A") (pintype "passive"))
      (node (ref "R13") (pin "1") (pinfunction "1_1") (pintype "passive"))
      (node (ref "U$17") (pin "2") (pinfunction "D_2") (pintype "passive"))
    )
    (net (code "22") (name "Net-(U$17-G)") (class "Default")
      (node (ref "R5") (pin "2") (pinfunction "2_2") (pintype "passive"))
      (node (ref "U$17") (pin "1") (pinfunction "G_1") (pintype "passive"))
    )
    (net (code "23") (name "Net-(U$18-G)") (class "Default")
      (node (ref "R7") (pin "2") (pinfunction "2_2") (pintype "passive"))
      (node (ref "U$18") (pin "1") (pinfunction "G_1") (pintype "passive"))
    )
    (net (code "24") (name "Net-(U$18-S)") (class "Default")
      (node (ref "U$18") (pin "3") (pinfunction "S_3") (pintype "passive"))
      (node (ref "U$19") (pin "2") (pinfunction "D_2") (pintype "passive"))
    )
    (net (code "25") (name "Net-(U$19-G)") (class "Default")
      (node (ref "R9") (pin "2") (pinfunction "2_2") (pintype "passive"))
      (node (ref "U$19") (pin "1") (pinfunction "G_1") (pintype "passive"))
    )
    (net (code "26") (name "Net-(U$22-A)") (class "Default")
      (node (ref "D5") (pin "A") (pinfunction "A_A") (pintype "passive"))
      (node (ref "U$22") (pin "3") (pinfunction "A_3") (pintype "bidirectional"))
    )
    (net (code "27") (name "Net-(U$22-K)") (class "Default")
      (node (ref "R16") (pin "2") (pinfunction "2_2") (pintype "passive"))
      (node (ref "U$22") (pin "2") (pinfunction "K_2") (pintype "bidirectional"))
    )
    (net (code "28") (name "Net-(X5C-S)") (class "Default")
      (node (ref "1A_500V_FUSE_ENERGYMETER") (pin "P$2") (pinfunction "P$2_P$2") (pintype "bidirectional"))
      (node (ref "X5") (pin "3") (pinfunction "S_3") (pintype "passive"))
    )
    (net (code "29") (name "Net-(X5G-S)") (class "Default")
      (node (ref "1A_500V_FUSE_IMD_VSENSE") (pin "P$2") (pinfunction "P$2_P$2") (pintype "bidirectional"))
      (node (ref "X5") (pin "7") (pinfunction "S_7") (pintype "passive"))
    )
    (net (code "30") (name "PRECHARGE+") (class "Default")
      (node (ref "U$9") (pin "A1") (pinfunction "A1_A1") (pintype "passive"))
      (node (ref "U$9") (pin "A10") (pinfunction "A10_A10") (pintype "passive"))
      (node (ref "U$9") (pin "A11") (pinfunction "A11_A11") (pintype "passive"))
      (node (ref "U$9") (pin "A12") (pinfunction "A12_A12") (pintype "passive"))
      (node (ref "U$9") (pin "A13") (pinfunction "A13_A13") (pintype "passive"))
      (node (ref "U$9") (pin "A14") (pinfunction "A14_A14") (pintype "passive"))
      (node (ref "U$9") (pin "A15") (pinfunction "A15_A15") (pintype "passive"))
      (node (ref "U$9") (pin "A16") (pinfunction "A16_A16") (pintype "passive"))
      (node (ref "U$9") (pin "A17") (pinfunction "A17_A17") (pintype "passive"))
      (node (ref "U$9") (pin "A18") (pinfunction "A18_A18") (pintype "passive"))
      (node (ref "U$9") (pin "A2") (pinfunction "A2_A2") (pintype "passive"))
      (node (ref "U$9") (pin "A3") (pinfunction "A3_A3") (pintype "passive"))
      (node (ref "U$9") (pin "A4") (pinfunction "A4_A4") (pintype "passive"))
      (node (ref "U$9") (pin "A5") (pinfunction "A5_A5") (pintype "passive"))
      (node (ref "U$9") (pin "A6") (pinfunction "A6_A6") (pintype "passive"))
      (node (ref "U$9") (pin "A7") (pinfunction "A7_A7") (pintype "passive"))
      (node (ref "U$9") (pin "A8") (pinfunction "A8_A8") (pintype "passive"))
      (node (ref "U$9") (pin "A9") (pinfunction "A9_A9") (pintype "passive"))
      (node (ref "X1") (pin "14") (pinfunction "S_14") (pintype "passive"))
    )
    (net (code "31") (name "RST1IN") (class "Default")
      (node (ref "U$13") (pin "NOB2") (pinfunction "NOB2_NOB2") (pintype "bidirectional"))
      (node (ref "U$14") (pin "COIL+") (pinfunction "COIL+_COIL+") (pintype "bidirectional"))
    )
    (net (code "32") (name "RST2IN") (class "Default")
      (node (ref "U$13") (pin "COIL-") (pinfunction "COIL-_COIL-") (pintype "bidirectional"))
      (node (ref "U$14") (pin "NOA2") (pinfunction "NOA2_NOA2") (pintype "bidirectional"))
    )
    (net (code "33") (name "SAFETY+") (class "Default")
      (node (ref "D1") (pin "1") (pinfunction "C_1") (pintype "passive"))
      (node (ref "R1") (pin "1") (pinfunction "1_1") (pintype "passive"))
      (node (ref "U$4") (pin "B1") (pinfunction "B1_B1") (pintype "passive"))
      (node (ref "U$4") (pin "B10") (pinfunction "B10_B10") (pintype "passive"))
      (node (ref "U$4") (pin "B11") (pinfunction "B11_B11") (pintype "passive"))
      (node (ref "U$4") (pin "B2") (pinfunction "B2_B2") (pintype "passive"))
      (node (ref "U$4") (pin "B3") (pinfunction "B3_B3") (pintype "passive"))
      (node (ref "U$4") (pin "B4") (pinfunction "B4_B4") (pintype "passive"))
      (node (ref "U$4") (pin "B5") (pinfunction "B5_B5") (pintype "passive"))
      (node (ref "U$4") (pin "B6") (pinfunction "B6_B6") (pintype "passive"))
      (node (ref "U$4") (pin "B7") (pinfunction "B7_B7") (pintype "passive"))
      (node (ref "U$4") (pin "B8") (pinfunction "B8_B8") (pintype "passive"))
      (node (ref "U$4") (pin "B9") (pinfunction "B9_B9") (pintype "passive"))
      (node (ref "X1") (pin "1") (pinfunction "S_1") (pintype "passive"))
    )
    (net (code "34") (name "SAFETY-") (class "Default")
      (node (ref "C2") (pin "2") (pinfunction "2_2") (pintype "passive"))
      (node (ref "U$5") (pin "B12") (pinfunction "B12_B12") (pintype "passive"))
      (node (ref "U$5") (pin "B13") (pinfunction "B13_B13") (pintype "passive"))
      (node (ref "U$5") (pin "B14") (pinfunction "B14_B14") (pintype "passive"))
      (node (ref "U$5") (pin "B15") (pinfunction "B15_B15") (pintype "passive"))
      (node (ref "U$5") (pin "B16") (pinfunction "B16_B16") (pintype "passive"))
      (node (ref "U$5") (pin "B17") (pinfunction "B17_B17") (pintype "passive"))
      (node (ref "U$5") (pin "B18") (pinfunction "B18_B18") (pintype "passive"))
      (node (ref "X1") (pin "13") (pinfunction "S_13") (pintype "passive"))
    )
    (net (code "35") (name "TSAL_GRN_GND") (class "Default")
      (node (ref "R5") (pin "1") (pinfunction "1_1") (pintype "passive"))
      (node (ref "R6") (pin "2") (pinfunction "2_2") (pintype "passive"))
      (node (ref "U$16") (pin "2") (pinfunction "D_2") (pintype "passive"))
      (node (ref "X1") (pin "10") (pinfunction "S_10") (pintype "passive"))
    )
    (net (code "36") (name "TSAL_RED_GND") (class "Default")
      (node (ref "U$18") (pin "2") (pinfunction "D_2") (pintype "passive"))
      (node (ref "X1") (pin "12") (pinfunction "S_12") (pintype "passive"))
    )
    (net (code "37") (name "V+") (class "Default")
      (node (ref "HV+_FUSE_DRY") (pin "P$2") (pinfunction "P$2_P$2") (pintype "bidirectional"))
      (node (ref "X5") (pin "1") (pinfunction "S_1") (pintype "passive"))
      (node (ref "X5") (pin "5") (pinfunction "S_5") (pintype "passive"))
    )
    (net (code "38") (name "V-") (class "Default")
      (node (ref "1A_500V_FUSE_ENERGYMETER") (pin "P$1") (pinfunction "P$1_P$1") (pintype "bidirectional"))
      (node (ref "1A_500V_FUSE_IMD_VSENSE") (pin "P$1") (pinfunction "P$1_P$1") (pintype "bidirectional"))
      (node (ref "OK3") (pin "2") (pinfunction "C_2") (pintype "passive"))
      (node (ref "U$22") (pin "1") (pinfunction "G_1") (pintype "bidirectional"))
      (node (ref "X5") (pin "4") (pinfunction "S_4") (pintype "passive"))
      (node (ref "X5") (pin "8") (pinfunction "S_8") (pintype "passive"))
    )
    (net (code "39") (name "unconnected-(U$3-PadA1)") (class "Default")
      (node (ref "U$3") (pin "A1") (pinfunction "A1_A1") (pintype "passive"))
    )
    (net (code "40") (name "unconnected-(U$3-PadA2)") (class "Default")
      (node (ref "U$3") (pin "A2") (pinfunction "A2_A2") (pintype "passive"))
    )
    (net (code "41") (name "unconnected-(U$3-PadA3)") (class "Default")
      (node (ref "U$3") (pin "A3") (pinfunction "A3_A3") (pintype "passive"))
    )
    (net (code "42") (name "unconnected-(U$3-PadA4)") (class "Default")
      (node (ref "U$3") (pin "A4") (pinfunction "A4_A4") (pintype "passive"))
    )
    (net (code "43") (name "unconnected-(U$3-PadA5)") (class "Default")
      (node (ref "U$3") (pin "A5") (pinfunction "A5_A5") (pintype "passive"))
    )
    (net (code "44") (name "unconnected-(U$3-PadA6)") (class "Default")
      (node (ref "U$3") (pin "A6") (pinfunction "A6_A6") (pintype "passive"))
    )
    (net (code "45") (name "unconnected-(U$3-PadA7)") (class "Default")
      (node (ref "U$3") (pin "A7") (pinfunction "A7_A7") (pintype "passive"))
    )
    (net (code "46") (name "unconnected-(U$3-PadA8)") (class "Default")
      (node (ref "U$3") (pin "A8") (pinfunction "A8_A8") (pintype "passive"))
    )
    (net (code "47") (name "unconnected-(U$3-PadA9)") (class "Default")
      (node (ref "U$3") (pin "A9") (pinfunction "A9_A9") (pintype "passive"))
    )
    (net (code "48") (name "unconnected-(U$3-PadA10)") (class "Default")
      (node (ref "U$3") (pin "A10") (pinfunction "A10_A10") (pintype "passive"))
    )
    (net (code "49") (name "unconnected-(U$3-PadA11)") (class "Default")
      (node (ref "U$3") (pin "A11") (pinfunction "A11_A11") (pintype "passive"))
    )
    (net (code "50") (name "unconnected-(U$3-PadA12)") (class "Default")
      (node (ref "U$3") (pin "A12") (pinfunction "A12_A12") (pintype "passive"))
    )
    (net (code "51") (name "unconnected-(U$3-PadA13)") (class "Default")
      (node (ref "U$3") (pin "A13") (pinfunction "A13_A13") (pintype "passive"))
    )
    (net (code "52") (name "unconnected-(U$3-PadA14)") (class "Default")
      (node (ref "U$3") (pin "A14") (pinfunction "A14_A14") (pintype "passive"))
    )
    (net (code "53") (name "unconnected-(U$3-PadA15)") (class "Default")
      (node (ref "U$3") (pin "A15") (pinfunction "A15_A15") (pintype "passive"))
    )
    (net (code "54") (name "unconnected-(U$3-PadA16)") (class "Default")
      (node (ref "U$3") (pin "A16") (pinfunction "A16_A16") (pintype "passive"))
    )
    (net (code "55") (name "unconnected-(U$3-PadA17)") (class "Default")
      (node (ref "U$3") (pin "A17") (pinfunction "A17_A17") (pintype "passive"))
    )
    (net (code "56") (name "unconnected-(U$3-PadA18)") (class "Default")
      (node (ref "U$3") (pin "A18") (pinfunction "A18_A18") (pintype "passive"))
    )
    (net (code "57") (name "unconnected-(U$3-PadB1)") (class "Default")
      (node (ref "U$3") (pin "B1") (pinfunction "B1_B1") (pintype "passive"))
    )
    (net (code "58") (name "unconnected-(U$3-PadB2)") (class "Default")
      (node (ref "U$3") (pin "B2") (pinfunction "B2_B2") (pintype "passive"))
    )
    (net (code "59") (name "unconnected-(U$3-PadB3)") (class "Default")
      (node (ref "U$3") (pin "B3") (pinfunction "B3_B3") (pintype "passive"))
    )
    (net (code "60") (name "unconnected-(U$3-PadB4)") (class "Default")
      (node (ref "U$3") (pin "B4") (pinfunction "B4_B4") (pintype "passive"))
    )
    (net (code "61") (name "unconnected-(U$3-PadB5)") (class "Default")
      (node (ref "U$3") (pin "B5") (pinfunction "B5_B5") (pintype "passive"))
    )
    (net (code "62") (name "unconnected-(U$3-PadB6)") (class "Default")
      (node (ref "U$3") (pin "B6") (pinfunction "B6_B6") (pintype "passive"))
    )
    (net (code "63") (name "unconnected-(U$3-PadB7)") (class "Default")
      (node (ref "U$3") (pin "B7") (pinfunction "B7_B7") (pintype "passive"))
    )
    (net (code "64") (name "unconnected-(U$3-PadB8)") (class "Default")
      (node (ref "U$3") (pin "B8") (pinfunction "B8_B8") (pintype "passive"))
    )
    (net (code "65") (name "unconnected-(U$3-PadB9)") (class "Default")
      (node (ref "U$3") (pin "B9") (pinfunction "B9_B9") (pintype "passive"))
    )
    (net (code "66") (name "unconnected-(U$3-PadB10)") (class "Default")
      (node (ref "U$3") (pin "B10") (pinfunction "B10_B10") (pintype "passive"))
    )
    (net (code "67") (name "unconnected-(U$3-PadB11)") (class "Default")
      (node (ref "U$3") (pin "B11") (pinfunction "B11_B11") (pintype "passive"))
    )
    (net (code "68") (name "unconnected-(U$3-PadB12)") (class "Default")
      (node (ref "U$3") (pin "B12") (pinfunction "B12_B12") (pintype "passive"))
    )
    (net (code "69") (name "unconnected-(U$3-PadB13)") (class "Default")
      (node (ref "U$3") (pin "B13") (pinfunction "B13_B13") (pintype "passive"))
    )
    (net (code "70") (name "unconnected-(U$3-PadB14)") (class "Default")
      (node (ref "U$3") (pin "B14") (pinfunction "B14_B14") (pintype "passive"))
    )
    (net (code "71") (name "unconnected-(U$3-PadB15)") (class "Default")
      (node (ref "U$3") (pin "B15") (pinfunction "B15_B15") (pintype "passive"))
    )
    (net (code "72") (name "unconnected-(U$3-PadB16)") (class "Default")
      (node (ref "U$3") (pin "B16") (pinfunction "B16_B16") (pintype "passive"))
    )
    (net (code "73") (name "unconnected-(U$3-PadB17)") (class "Default")
      (node (ref "U$3") (pin "B17") (pinfunction "B17_B17") (pintype "passive"))
    )
    (net (code "74") (name "unconnected-(U$3-PadB18)") (class "Default")
      (node (ref "U$3") (pin "B18") (pinfunction "B18_B18") (pintype "passive"))
    )
    (net (code "75") (name "unconnected-(U$5-PadA1)") (class "Default")
      (node (ref "U$5") (pin "A1") (pinfunction "A1_A1") (pintype "passive"))
    )
    (net (code "76") (name "unconnected-(U$5-PadA2)") (class "Default")
      (node (ref "U$5") (pin "A2") (pinfunction "A2_A2") (pintype "passive"))
    )
    (net (code "77") (name "unconnected-(U$5-PadA3)") (class "Default")
      (node (ref "U$5") (pin "A3") (pinfunction "A3_A3") (pintype "passive"))
    )
    (net (code "78") (name "unconnected-(U$5-PadA4)") (class "Default")
      (node (ref "U$5") (pin "A4") (pinfunction "A4_A4") (pintype "passive"))
    )
    (net (code "79") (name "unconnected-(U$5-PadA5)") (class "Default")
      (node (ref "U$5") (pin "A5") (pinfunction "A5_A5") (pintype "passive"))
    )
    (net (code "80") (name "unconnected-(U$5-PadA6)") (class "Default")
      (node (ref "U$5") (pin "A6") (pinfunction "A6_A6") (pintype "passive"))
    )
    (net (code "81") (name "unconnected-(U$5-PadA7)") (class "Default")
      (node (ref "U$5") (pin "A7") (pinfunction "A7_A7") (pintype "passive"))
    )
    (net (code "82") (name "unconnected-(U$5-PadA8)") (class "Default")
      (node (ref "U$5") (pin "A8") (pinfunction "A8_A8") (pintype "passive"))
    )
    (net (code "83") (name "unconnected-(U$5-PadA9)") (class "Default")
      (node (ref "U$5") (pin "A9") (pinfunction "A9_A9") (pintype "passive"))
    )
    (net (code "84") (name "unconnected-(U$5-PadA10)") (class "Default")
      (node (ref "U$5") (pin "A10") (pinfunction "A10_A10") (pintype "passive"))
    )
    (net (code "85") (name "unconnected-(U$5-PadA11)") (class "Default")
      (node (ref "U$5") (pin "A11") (pinfunction "A11_A11") (pintype "passive"))
    )
    (net (code "86") (name "unconnected-(U$5-PadA12)") (class "Default")
      (node (ref "U$5") (pin "A12") (pinfunction "A12_A12") (pintype "passive"))
    )
    (net (code "87") (name "unconnected-(U$5-PadA13)") (class "Default")
      (node (ref "U$5") (pin "A13") (pinfunction "A13_A13") (pintype "passive"))
    )
    (net (code "88") (name "unconnected-(U$5-PadA14)") (class "Default")
      (node (ref "U$5") (pin "A14") (pinfunction "A14_A14") (pintype "passive"))
    )
    (net (code "89") (name "unconnected-(U$5-PadA15)") (class "Default")
      (node (ref "U$5") (pin "A15") (pinfunction "A15_A15") (pintype "passive"))
    )
    (net (code "90") (name "unconnected-(U$5-PadA16)") (class "Default")
      (node (ref "U$5") (pin "A16") (pinfunction "A16_A16") (pintype "passive"))
    )
    (net (code "91") (name "unconnected-(U$5-PadA17)") (class "Default")
      (node (ref "U$5") (pin "A17") (pinfunction "A17_A17") (pintype "passive"))
    )
    (net (code "92") (name "unconnected-(U$5-PadA18)") (class "Default")
      (node (ref "U$5") (pin "A18") (pinfunction "A18_A18") (pintype "passive"))
    )
    (net (code "93") (name "unconnected-(U$6-PadA1)") (class "Default")
      (node (ref "U$6") (pin "A1") (pinfunction "A1_A1") (pintype "passive"))
    )
    (net (code "94") (name "unconnected-(U$6-PadA2)") (class "Default")
      (node (ref "U$6") (pin "A2") (pinfunction "A2_A2") (pintype "passive"))
    )
    (net (code "95") (name "unconnected-(U$6-PadA3)") (class "Default")
      (node (ref "U$6") (pin "A3") (pinfunction "A3_A3") (pintype "passive"))
    )
    (net (code "96") (name "unconnected-(U$6-PadA4)") (class "Default")
      (node (ref "U$6") (pin "A4") (pinfunction "A4_A4") (pintype "passive"))
    )
    (net (code "97") (name "unconnected-(U$6-PadA5)") (class "Default")
      (node (ref "U$6") (pin "A5") (pinfunction "A5_A5") (pintype "passive"))
    )
    (net (code "98") (name "unconnected-(U$6-PadA6)") (class "Default")
      (node (ref "U$6") (pin "A6") (pinfunction "A6_A6") (pintype "passive"))
    )
    (net (code "99") (name "unconnected-(U$6-PadA7)") (class "Default")
      (node (ref "U$6") (pin "A7") (pinfunction "A7_A7") (pintype "passive"))
    )
    (net (code "100") (name "unconnected-(U$6-PadA8)") (class "Default")
      (node (ref "U$6") (pin "A8") (pinfunction "A8_A8") (pintype "passive"))
    )
    (net (code "101") (name "unconnected-(U$6-PadA9)") (class "Default")
      (node (ref "U$6") (pin "A9") (pinfunction "A9_A9") (pintype "passive"))
    )
    (net (code "102") (name "unconnected-(U$6-PadA10)") (class "Default")
      (node (ref "U$6") (pin "A10") (pinfunction "A10_A10") (pintype "passive"))
    )
    (net (code "103") (name "unconnected-(U$6-PadA11)") (class "Default")
      (node (ref "U$6") (pin "A11") (pinfunction "A11_A11") (pintype "passive"))
    )
    (net (code "104") (name "unconnected-(U$6-PadA12)") (class "Default")
      (node (ref "U$6") (pin "A12") (pinfunction "A12_A12") (pintype "passive"))
    )
    (net (code "105") (name "unconnected-(U$6-PadA13)") (class "Default")
      (node (ref "U$6") (pin "A13") (pinfunction "A13_A13") (pintype "passive"))
    )
    (net (code "106") (name "unconnected-(U$6-PadA14)") (class "Default")
      (node (ref "U$6") (pin "A14") (pinfunction "A14_A14") (pintype "passive"))
    )
    (net (code "107") (name "unconnected-(U$6-PadA15)") (class "Default")
      (node (ref "U$6") (pin "A15") (pinfunction "A15_A15") (pintype "passive"))
    )
    (net (code "108") (name "unconnected-(U$6-PadA16)") (class "Default")
      (node (ref "U$6") (pin "A16") (pinfunction "A16_A16") (pintype "passive"))
    )
    (net (code "109") (name "unconnected-(U$6-PadA17)") (class "Default")
      (node (ref "U$6") (pin "A17") (pinfunction "A17_A17") (pintype "passive"))
    )
    (net (code "110") (name "unconnected-(U$6-PadA18)") (class "Default")
      (node (ref "U$6") (pin "A18") (pinfunction "A18_A18") (pintype "passive"))
    )
    (net (code "111") (name "unconnected-(U$6-PadB1)") (class "Default")
      (node (ref "U$6") (pin "B1") (pinfunction "B1_B1") (pintype "passive"))
    )
    (net (code "112") (name "unconnected-(U$6-PadB2)") (class "Default")
      (node (ref "U$6") (pin "B2") (pinfunction "B2_B2") (pintype "passive"))
    )
    (net (code "113") (name "unconnected-(U$6-PadB3)") (class "Default")
      (node (ref "U$6") (pin "B3") (pinfunction "B3_B3") (pintype "passive"))
    )
    (net (code "114") (name "unconnected-(U$6-PadB4)") (class "Default")
      (node (ref "U$6") (pin "B4") (pinfunction "B4_B4") (pintype "passive"))
    )
    (net (code "115") (name "unconnected-(U$6-PadB5)") (class "Default")
      (node (ref "U$6") (pin "B5") (pinfunction "B5_B5") (pintype "passive"))
    )
    (net (code "116") (name "unconnected-(U$6-PadB6)") (class "Default")
      (node (ref "U$6") (pin "B6") (pinfunction "B6_B6") (pintype "passive"))
    )
    (net (code "117") (name "unconnected-(U$6-PadB7)") (class "Default")
      (node (ref "U$6") (pin "B7") (pinfunction "B7_B7") (pintype "passive"))
    )
    (net (code "118") (name "unconnected-(U$6-PadB8)") (class "Default")
      (node (ref "U$6") (pin "B8") (pinfunction "B8_B8") (pintype "passive"))
    )
    (net (code "119") (name "unconnected-(U$6-PadB9)") (class "Default")
      (node (ref "U$6") (pin "B9") (pinfunction "B9_B9") (pintype "passive"))
    )
    (net (code "120") (name "unconnected-(U$6-PadB10)") (class "Default")
      (node (ref "U$6") (pin "B10") (pinfunction "B10_B10") (pintype "passive"))
    )
    (net (code "121") (name "unconnected-(U$6-PadB11)") (class "Default")
      (node (ref "U$6") (pin "B11") (pinfunction "B11_B11") (pintype "passive"))
    )
    (net (code "122") (name "unconnected-(U$6-PadB12)") (class "Default")
      (node (ref "U$6") (pin "B12") (pinfunction "B12_B12") (pintype "passive"))
    )
    (net (code "123") (name "unconnected-(U$6-PadB13)") (class "Default")
      (node (ref "U$6") (pin "B13") (pinfunction "B13_B13") (pintype "passive"))
    )
    (net (code "124") (name "unconnected-(U$6-PadB14)") (class "Default")
      (node (ref "U$6") (pin "B14") (pinfunction "B14_B14") (pintype "passive"))
    )
    (net (code "125") (name "unconnected-(U$6-PadB15)") (class "Default")
      (node (ref "U$6") (pin "B15") (pinfunction "B15_B15") (pintype "passive"))
    )
    (net (code "126") (name "unconnected-(U$6-PadB16)") (class "Default")
      (node (ref "U$6") (pin "B16") (pinfunction "B16_B16") (pintype "passive"))
    )
    (net (code "127") (name "unconnected-(U$6-PadB17)") (class "Default")
      (node (ref "U$6") (pin "B17") (pinfunction "B17_B17") (pintype "passive"))
    )
    (net (code "128") (name "unconnected-(U$6-PadB18)") (class "Default")
      (node (ref "U$6") (pin "B18") (pinfunction "B18_B18") (pintype "passive"))
    )
    (net (code "129") (name "unconnected-(U$8-PadA1)") (class "Default")
      (node (ref "U$8") (pin "A1") (pinfunction "A1_A1") (pintype "passive"))
    )
    (net (code "130") (name "unconnected-(U$8-PadA2)") (class "Default")
      (node (ref "U$8") (pin "A2") (pinfunction "A2_A2") (pintype "passive"))
    )
    (net (code "131") (name "unconnected-(U$8-PadA3)") (class "Default")
      (node (ref "U$8") (pin "A3") (pinfunction "A3_A3") (pintype "passive"))
    )
    (net (code "132") (name "unconnected-(U$8-PadA4)") (class "Default")
      (node (ref "U$8") (pin "A4") (pinfunction "A4_A4") (pintype "passive"))
    )
    (net (code "133") (name "unconnected-(U$8-PadA5)") (class "Default")
      (node (ref "U$8") (pin "A5") (pinfunction "A5_A5") (pintype "passive"))
    )
    (net (code "134") (name "unconnected-(U$8-PadA6)") (class "Default")
      (node (ref "U$8") (pin "A6") (pinfunction "A6_A6") (pintype "passive"))
    )
    (net (code "135") (name "unconnected-(U$8-PadA7)") (class "Default")
      (node (ref "U$8") (pin "A7") (pinfunction "A7_A7") (pintype "passive"))
    )
    (net (code "136") (name "unconnected-(U$8-PadA8)") (class "Default")
      (node (ref "U$8") (pin "A8") (pinfunction "A8_A8") (pintype "passive"))
    )
    (net (code "137") (name "unconnected-(U$8-PadA9)") (class "Default")
      (node (ref "U$8") (pin "A9") (pinfunction "A9_A9") (pintype "passive"))
    )
    (net (code "138") (name "unconnected-(U$8-PadA10)") (class "Default")
      (node (ref "U$8") (pin "A10") (pinfunction "A10_A10") (pintype "passive"))
    )
    (net (code "139") (name "unconnected-(U$8-PadA11)") (class "Default")
      (node (ref "U$8") (pin "A11") (pinfunction "A11_A11") (pintype "passive"))
    )
    (net (code "140") (name "unconnected-(U$8-PadA12)") (class "Default")
      (node (ref "U$8") (pin "A12") (pinfunction "A12_A12") (pintype "passive"))
    )
    (net (code "141") (name "unconnected-(U$8-PadA13)") (class "Default")
      (node (ref "U$8") (pin "A13") (pinfunction "A13_A13") (pintype "passive"))
    )
    (net (code "142") (name "unconnected-(U$8-PadA14)") (class "Default")
      (node (ref "U$8") (pin "A14") (pinfunction "A14_A14") (pintype "passive"))
    )
    (net (code "143") (name "unconnected-(U$8-PadA15)") (class "Default")
      (node (ref "U$8") (pin "A15") (pinfunction "A15_A15") (pintype "passive"))
    )
    (net (code "144") (name "unconnected-(U$8-PadA16)") (class "Default")
      (node (ref "U$8") (pin "A16") (pinfunction "A16_A16") (pintype "passive"))
    )
    (net (code "145") (name "unconnected-(U$8-PadA17)") (class "Default")
      (node (ref "U$8") (pin "A17") (pinfunction "A17_A17") (pintype "passive"))
    )
    (net (code "146") (name "unconnected-(U$8-PadA18)") (class "Default")
      (node (ref "U$8") (pin "A18") (pinfunction "A18_A18") (pintype "passive"))
    )
    (net (code "147") (name "unconnected-(U$8-PadB1)") (class "Default")
      (node (ref "U$8") (pin "B1") (pinfunction "B1_B1") (pintype "passive"))
    )
    (net (code "148") (name "unconnected-(U$8-PadB2)") (class "Default")
      (node (ref "U$8") (pin "B2") (pinfunction "B2_B2") (pintype "passive"))
    )
    (net (code "149") (name "unconnected-(U$8-PadB3)") (class "Default")
      (node (ref "U$8") (pin "B3") (pinfunction "B3_B3") (pintype "passive"))
    )
    (net (code "150") (name "unconnected-(U$8-PadB4)") (class "Default")
      (node (ref "U$8") (pin "B4") (pinfunction "B4_B4") (pintype "passive"))
    )
    (net (code "151") (name "unconnected-(U$8-PadB5)") (class "Default")
      (node (ref "U$8") (pin "B5") (pinfunction "B5_B5") (pintype "passive"))
    )
    (net (code "152") (name "unconnected-(U$8-PadB6)") (class "Default")
      (node (ref "U$8") (pin "B6") (pinfunction "B6_B6") (pintype "passive"))
    )
    (net (code "153") (name "unconnected-(U$8-PadB7)") (class "Default")
      (node (ref "U$8") (pin "B7") (pinfunction "B7_B7") (pintype "passive"))
    )
    (net (code "154") (name "unconnected-(U$8-PadB8)") (class "Default")
      (node (ref "U$8") (pin "B8") (pinfunction "B8_B8") (pintype "passive"))
    )
    (net (code "155") (name "unconnected-(U$8-PadB9)") (class "Default")
      (node (ref "U$8") (pin "B9") (pinfunction "B9_B9") (pintype "passive"))
    )
    (net (code "156") (name "unconnected-(U$8-PadB10)") (class "Default")
      (node (ref "U$8") (pin "B10") (pinfunction "B10_B10") (pintype "passive"))
    )
    (net (code "157") (name "unconnected-(U$8-PadB11)") (class "Default")
      (node (ref "U$8") (pin "B11") (pinfunction "B11_B11") (pintype "passive"))
    )
    (net (code "158") (name "unconnected-(U$8-PadB12)") (class "Default")
      (node (ref "U$8") (pin "B12") (pinfunction "B12_B12") (pintype "passive"))
    )
    (net (code "159") (name "unconnected-(U$8-PadB13)") (class "Default")
      (node (ref "U$8") (pin "B13") (pinfunction "B13_B13") (pintype "passive"))
    )
    (net (code "160") (name "unconnected-(U$8-PadB14)") (class "Default")
      (node (ref "U$8") (pin "B14") (pinfunction "B14_B14") (pintype "passive"))
    )
    (net (code "161") (name "unconnected-(U$8-PadB15)") (class "Default")
      (node (ref "U$8") (pin "B15") (pinfunction "B15_B15") (pintype "passive"))
    )
    (net (code "162") (name "unconnected-(U$8-PadB16)") (class "Default")
      (node (ref "U$8") (pin "B16") (pinfunction "B16_B16") (pintype "passive"))
    )
    (net (code "163") (name "unconnected-(U$8-PadB17)") (class "Default")
      (node (ref "U$8") (pin "B17") (pinfunction "B17_B17") (pintype "passive"))
    )
    (net (code "164") (name "unconnected-(U$8-PadB18)") (class "Default")
      (node (ref "U$8") (pin "B18") (pinfunction "B18_B18") (pintype "passive"))
    )
    (net (code "165") (name "unconnected-(U$10-PadA1)") (class "Default")
      (node (ref "U$10") (pin "A1") (pinfunction "A1_A1") (pintype "passive"))
    )
    (net (code "166") (name "unconnected-(U$10-PadA2)") (class "Default")
      (node (ref "U$10") (pin "A2") (pinfunction "A2_A2") (pintype "passive"))
    )
    (net (code "167") (name "unconnected-(U$10-PadA3)") (class "Default")
      (node (ref "U$10") (pin "A3") (pinfunction "A3_A3") (pintype "passive"))
    )
    (net (code "168") (name "unconnected-(U$10-PadA4)") (class "Default")
      (node (ref "U$10") (pin "A4") (pinfunction "A4_A4") (pintype "passive"))
    )
    (net (code "169") (name "unconnected-(U$10-PadA5)") (class "Default")
      (node (ref "U$10") (pin "A5") (pinfunction "A5_A5") (pintype "passive"))
    )
    (net (code "170") (name "unconnected-(U$10-PadA6)") (class "Default")
      (node (ref "U$10") (pin "A6") (pinfunction "A6_A6") (pintype "passive"))
    )
    (net (code "171") (name "unconnected-(U$10-PadA7)") (class "Default")
      (node (ref "U$10") (pin "A7") (pinfunction "A7_A7") (pintype "passive"))
    )
    (net (code "172") (name "unconnected-(U$10-PadA8)") (class "Default")
      (node (ref "U$10") (pin "A8") (pinfunction "A8_A8") (pintype "passive"))
    )
    (net (code "173") (name "unconnected-(U$10-PadA9)") (class "Default")
      (node (ref "U$10") (pin "A9") (pinfunction "A9_A9") (pintype "passive"))
    )
    (net (code "174") (name "unconnected-(U$10-PadA10)") (class "Default")
      (node (ref "U$10") (pin "A10") (pinfunction "A10_A10") (pintype "passive"))
    )
    (net (code "175") (name "unconnected-(U$10-PadA11)") (class "Default")
      (node (ref "U$10") (pin "A11") (pinfunction "A11_A11") (pintype "passive"))
    )
    (net (code "176") (name "unconnected-(U$10-PadA12)") (class "Default")
      (node (ref "U$10") (pin "A12") (pinfunction "A12_A12") (pintype "passive"))
    )
    (net (code "177") (name "unconnected-(U$10-PadA13)") (class "Default")
      (node (ref "U$10") (pin "A13") (pinfunction "A13_A13") (pintype "passive"))
    )
    (net (code "178") (name "unconnected-(U$10-PadA14)") (class "Default")
      (node (ref "U$10") (pin "A14") (pinfunction "A14_A14") (pintype "passive"))
    )
    (net (code "179") (name "unconnected-(U$10-PadA15)") (class "Default")
      (node (ref "U$10") (pin "A15") (pinfunction "A15_A15") (pintype "passive"))
    )
    (net (code "180") (name "unconnected-(U$10-PadA16)") (class "Default")
      (node (ref "U$10") (pin "A16") (pinfunction "A16_A16") (pintype "passive"))
    )
    (net (code "181") (name "unconnected-(U$10-PadA17)") (class "Default")
      (node (ref "U$10") (pin "A17") (pinfunction "A17_A17") (pintype "passive"))
    )
    (net (code "182") (name "unconnected-(U$10-PadA18)") (class "Default")
      (node (ref "U$10") (pin "A18") (pinfunction "A18_A18") (pintype "passive"))
    )
    (net (code "183") (name "unconnected-(U$10-PadB1)") (class "Default")
      (node (ref "U$10") (pin "B1") (pinfunction "B1_B1") (pintype "passive"))
    )
    (net (code "184") (name "unconnected-(U$10-PadB2)") (class "Default")
      (node (ref "U$10") (pin "B2") (pinfunction "B2_B2") (pintype "passive"))
    )
    (net (code "185") (name "unconnected-(U$10-PadB3)") (class "Default")
      (node (ref "U$10") (pin "B3") (pinfunction "B3_B3") (pintype "passive"))
    )
    (net (code "186") (name "unconnected-(U$10-PadB4)") (class "Default")
      (node (ref "U$10") (pin "B4") (pinfunction "B4_B4") (pintype "passive"))
    )
    (net (code "187") (name "unconnected-(U$10-PadB5)") (class "Default")
      (node (ref "U$10") (pin "B5") (pinfunction "B5_B5") (pintype "passive"))
    )
    (net (code "188") (name "unconnected-(U$10-PadB6)") (class "Default")
      (node (ref "U$10") (pin "B6") (pinfunction "B6_B6") (pintype "passive"))
    )
    (net (code "189") (name "unconnected-(U$10-PadB7)") (class "Default")
      (node (ref "U$10") (pin "B7") (pinfunction "B7_B7") (pintype "passive"))
    )
    (net (code "190") (name "unconnected-(U$10-PadB8)") (class "Default")
      (node (ref "U$10") (pin "B8") (pinfunction "B8_B8") (pintype "passive"))
    )
    (net (code "191") (name "unconnected-(U$10-PadB9)") (class "Default")
      (node (ref "U$10") (pin "B9") (pinfunction "B9_B9") (pintype "passive"))
    )
    (net (code "192") (name "unconnected-(U$10-PadB10)") (class "Default")
      (node (ref "U$10") (pin "B10") (pinfunction "B10_B10") (pintype "passive"))
    )
    (net (code "193") (name "unconnected-(U$10-PadB11)") (class "Default")
      (node (ref "U$10") (pin "B11") (pinfunction "B11_B11") (pintype "passive"))
    )
    (net (code "194") (name "unconnected-(U$10-PadB12)") (class "Default")
      (node (ref "U$10") (pin "B12") (pinfunction "B12_B12") (pintype "passive"))
    )
    (net (code "195") (name "unconnected-(U$10-PadB13)") (class "Default")
      (node (ref "U$10") (pin "B13") (pinfunction "B13_B13") (pintype "passive"))
    )
    (net (code "196") (name "unconnected-(U$10-PadB14)") (class "Default")
      (node (ref "U$10") (pin "B14") (pinfunction "B14_B14") (pintype "passive"))
    )
    (net (code "197") (name "unconnected-(U$10-PadB15)") (class "Default")
      (node (ref "U$10") (pin "B15") (pinfunction "B15_B15") (pintype "passive"))
    )
    (net (code "198") (name "unconnected-(U$10-PadB16)") (class "Default")
      (node (ref "U$10") (pin "B16") (pinfunction "B16_B16") (pintype "passive"))
    )
    (net (code "199") (name "unconnected-(U$10-PadB17)") (class "Default")
      (node (ref "U$10") (pin "B17") (pinfunction "B17_B17") (pintype "passive"))
    )
    (net (code "200") (name "unconnected-(U$10-PadB18)") (class "Default")
      (node (ref "U$10") (pin "B18") (pinfunction "B18_B18") (pintype "passive"))
    )
    (net (code "201") (name "unconnected-(U$11-PadA1)") (class "Default")
      (node (ref "U$11") (pin "A1") (pinfunction "A1_A1") (pintype "passive"))
    )
    (net (code "202") (name "unconnected-(U$11-PadA2)") (class "Default")
      (node (ref "U$11") (pin "A2") (pinfunction "A2_A2") (pintype "passive"))
    )
    (net (code "203") (name "unconnected-(U$11-PadA3)") (class "Default")
      (node (ref "U$11") (pin "A3") (pinfunction "A3_A3") (pintype "passive"))
    )
    (net (code "204") (name "unconnected-(U$11-PadA4)") (class "Default")
      (node (ref "U$11") (pin "A4") (pinfunction "A4_A4") (pintype "passive"))
    )
    (net (code "205") (name "unconnected-(U$11-PadA5)") (class "Default")
      (node (ref "U$11") (pin "A5") (pinfunction "A5_A5") (pintype "passive"))
    )
    (net (code "206") (name "unconnected-(U$11-PadA6)") (class "Default")
      (node (ref "U$11") (pin "A6") (pinfunction "A6_A6") (pintype "passive"))
    )
    (net (code "207") (name "unconnected-(U$11-PadA7)") (class "Default")
      (node (ref "U$11") (pin "A7") (pinfunction "A7_A7") (pintype "passive"))
    )
    (net (code "208") (name "unconnected-(U$11-PadA8)") (class "Default")
      (node (ref "U$11") (pin "A8") (pinfunction "A8_A8") (pintype "passive"))
    )
    (net (code "209") (name "unconnected-(U$11-PadA9)") (class "Default")
      (node (ref "U$11") (pin "A9") (pinfunction "A9_A9") (pintype "passive"))
    )
    (net (code "210") (name "unconnected-(U$11-PadA10)") (class "Default")
      (node (ref "U$11") (pin "A10") (pinfunction "A10_A10") (pintype "passive"))
    )
    (net (code "211") (name "unconnected-(U$11-PadA11)") (class "Default")
      (node (ref "U$11") (pin "A11") (pinfunction "A11_A11") (pintype "passive"))
    )
    (net (code "212") (name "unconnected-(U$11-PadA12)") (class "Default")
      (node (ref "U$11") (pin "A12") (pinfunction "A12_A12") (pintype "passive"))
    )
    (net (code "213") (name "unconnected-(U$11-PadA13)") (class "Default")
      (node (ref "U$11") (pin "A13") (pinfunction "A13_A13") (pintype "passive"))
    )
    (net (code "214") (name "unconnected-(U$11-PadA14)") (class "Default")
      (node (ref "U$11") (pin "A14") (pinfunction "A14_A14") (pintype "passive"))
    )
    (net (code "215") (name "unconnected-(U$11-PadA15)") (class "Default")
      (node (ref "U$11") (pin "A15") (pinfunction "A15_A15") (pintype "passive"))
    )
    (net (code "216") (name "unconnected-(U$11-PadA16)") (class "Default")
      (node (ref "U$11") (pin "A16") (pinfunction "A16_A16") (pintype "passive"))
    )
    (net (code "217") (name "unconnected-(U$11-PadA17)") (class "Default")
      (node (ref "U$11") (pin "A17") (pinfunction "A17_A17") (pintype "passive"))
    )
    (net (code "218") (name "unconnected-(U$11-PadA18)") (class "Default")
      (node (ref "U$11") (pin "A18") (pinfunction "A18_A18") (pintype "passive"))
    )
    (net (code "219") (name "unconnected-(U$11-PadB1)") (class "Default")
      (node (ref "U$11") (pin "B1") (pinfunction "B1_B1") (pintype "passive"))
    )
    (net (code "220") (name "unconnected-(U$11-PadB2)") (class "Default")
      (node (ref "U$11") (pin "B2") (pinfunction "B2_B2") (pintype "passive"))
    )
    (net (code "221") (name "unconnected-(U$11-PadB3)") (class "Default")
      (node (ref "U$11") (pin "B3") (pinfunction "B3_B3") (pintype "passive"))
    )
    (net (code "222") (name "unconnected-(U$11-PadB4)") (class "Default")
      (node (ref "U$11") (pin "B4") (pinfunction "B4_B4") (pintype "passive"))
    )
    (net (code "223") (name "unconnected-(U$11-PadB5)") (class "Default")
      (node (ref "U$11") (pin "B5") (pinfunction "B5_B5") (pintype "passive"))
    )
    (net (code "224") (name "unconnected-(U$11-PadB6)") (class "Default")
      (node (ref "U$11") (pin "B6") (pinfunction "B6_B6") (pintype "passive"))
    )
    (net (code "225") (name "unconnected-(U$11-PadB7)") (class "Default")
      (node (ref "U$11") (pin "B7") (pinfunction "B7_B7") (pintype "passive"))
    )
    (net (code "226") (name "unconnected-(U$11-PadB8)") (class "Default")
      (node (ref "U$11") (pin "B8") (pinfunction "B8_B8") (pintype "passive"))
    )
    (net (code "227") (name "unconnected-(U$11-PadB9)") (class "Default")
      (node (ref "U$11") (pin "B9") (pinfunction "B9_B9") (pintype "passive"))
    )
    (net (code "228") (name "unconnected-(U$11-PadB10)") (class "Default")
      (node (ref "U$11") (pin "B10") (pinfunction "B10_B10") (pintype "passive"))
    )
    (net (code "229") (name "unconnected-(U$11-PadB11)") (class "Default")
      (node (ref "U$11") (pin "B11") (pinfunction "B11_B11") (pintype "passive"))
    )
    (net (code "230") (name "unconnected-(U$11-PadB12)") (class "Default")
      (node (ref "U$11") (pin "B12") (pinfunction "B12_B12") (pintype "passive"))
    )
    (net (code "231") (name "unconnected-(U$11-PadB13)") (class "Default")
      (node (ref "U$11") (pin "B13") (pinfunction "B13_B13") (pintype "passive"))
    )
    (net (code "232") (name "unconnected-(U$11-PadB14)") (class "Default")
      (node (ref "U$11") (pin "B14") (pinfunction "B14_B14") (pintype "passive"))
    )
    (net (code "233") (name "unconnected-(U$11-PadB15)") (class "Default")
      (node (ref "U$11") (pin "B15") (pinfunction "B15_B15") (pintype "passive"))
    )
    (net (code "234") (name "unconnected-(U$11-PadB16)") (class "Default")
      (node (ref "U$11") (pin "B16") (pinfunction "B16_B16") (pintype "passive"))
    )
    (net (code "235") (name "unconnected-(U$11-PadB17)") (class "Default")
      (node (ref "U$11") (pin "B17") (pinfunction "B17_B17") (pintype "passive"))
    )
    (net (code "236") (name "unconnected-(U$11-PadB18)") (class "Default")
      (node (ref "U$11") (pin "B18") (pinfunction "B18_B18") (pintype "passive"))
    )
    (net (code "237") (name "unconnected-(U$13-PadNCA4)") (class "Default")
      (node (ref "U$13") (pin "NCA4") (pinfunction "NCA4_NCA4") (pintype "bidirectional"))
    )
    (net (code "238") (name "unconnected-(U$13-PadNCB4)") (class "Default")
      (node (ref "U$13") (pin "NCB4") (pinfunction "NCB4_NCB4") (pintype "bidirectional"))
    )
    (net (code "239") (name "unconnected-(U$13-PadNOA1)") (class "Default")
      (node (ref "U$13") (pin "NOA1") (pinfunction "NOA1_NOA1") (pintype "bidirectional"))
    )
    (net (code "240") (name "unconnected-(U$13-PadNOB1)") (class "Default")
      (node (ref "U$13") (pin "NOB1") (pinfunction "NOB1_NOB1") (pintype "bidirectional"))
    )
    (net (code "241") (name "unconnected-(U$14-PadNCA4)") (class "Default")
      (node (ref "U$14") (pin "NCA4") (pinfunction "NCA4_NCA4") (pintype "bidirectional"))
    )
    (net (code "242") (name "unconnected-(U$14-PadNCB4)") (class "Default")
      (node (ref "U$14") (pin "NCB4") (pinfunction "NCB4_NCB4") (pintype "bidirectional"))
    )
    (net (code "243") (name "unconnected-(U$14-PadNOA1)") (class "Default")
      (node (ref "U$14") (pin "NOA1") (pinfunction "NOA1_NOA1") (pintype "bidirectional"))
    )
    (net (code "244") (name "unconnected-(U$14-PadNOB1)") (class "Default")
      (node (ref "U$14") (pin "NOB1") (pinfunction "NOB1_NOB1") (pintype "bidirectional"))
    )
    (net (code "245") (name "unconnected-(U$14-PadNOB3)") (class "Default")
      (node (ref "U$14") (pin "NOB3") (pinfunction "NOB3_NOB3") (pintype "bidirectional"))
    )
    (net (code "246") (name "unconnected-(X1G-S-Pad15)") (class "Default")
      (node (ref "X1") (pin "15") (pinfunction "S_15") (pintype "passive"))
    )
    (net (code "247") (name "unconnected-(X1H-S-Pad16)") (class "Default")
      (node (ref "X1") (pin "16") (pinfunction "S_16") (pintype "passive"))
    )
    (net (code "248") (name "unconnected-(X1I-S-Pad17)") (class "Default")
      (node (ref "X1") (pin "17") (pinfunction "S_17") (pintype "passive"))
    )
    (net (code "249") (name "unconnected-(X1J-S-Pad18)") (class "Default")
      (node (ref "X1") (pin "18") (pinfunction "S_18") (pintype "passive"))
    )
    (net (code "250") (name "unconnected-(X1K-S-Pad19)") (class "Default")
      (node (ref "X1") (pin "19") (pinfunction "S_19") (pintype "passive"))
    )
    (net (code "251") (name "unconnected-(X1M-S-Pad20)") (class "Default")
      (node (ref "X1") (pin "20") (pinfunction "S_20") (pintype "passive"))
    )
    (net (code "252") (name "unconnected-(X1N-S-Pad21)") (class "Default")
      (node (ref "X1") (pin "21") (pinfunction "S_21") (pintype "passive"))
    )
    (net (code "253") (name "unconnected-(X1O-S-Pad22)") (class "Default")
      (node (ref "X1") (pin "22") (pinfunction "S_22") (pintype "passive"))
    )
    (net (code "254") (name "unconnected-(X1P-S-Pad23)") (class "Default")
      (node (ref "X1") (pin "23") (pinfunction "S_23") (pintype "passive"))
    )
    (net (code "255") (name "unconnected-(X1R-S-Pad3)") (class "Default")
      (node (ref "X1") (pin "3") (pinfunction "S_3") (pintype "passive"))
    )
    (net (code "256") (name "unconnected-(X1S-S-Pad4)") (class "Default")
      (node (ref "X1") (pin "4") (pinfunction "S_4") (pintype "passive"))
    )
    (net (code "257") (name "unconnected-(X1T-S-Pad5)") (class "Default")
      (node (ref "X1") (pin "5") (pinfunction "S_5") (pintype "passive"))
    )
    (net (code "258") (name "unconnected-(X1U-S-Pad6)") (class "Default")
      (node (ref "X1") (pin "6") (pinfunction "S_6") (pintype "passive"))
    )
    (net (code "259") (name "unconnected-(X1V-S-Pad7)") (class "Default")
      (node (ref "X1") (pin "7") (pinfunction "S_7") (pintype "passive"))
    )
    (net (code "260") (name "unconnected-(X1W-S-Pad8)") (class "Default")
      (node (ref "X1") (pin "8") (pinfunction "S_8") (pintype "passive"))
    )
    (net (code "261") (name "unconnected-(X1X-S-Pad9)") (class "Default")
      (node (ref "X1") (pin "9") (pinfunction "S_9") (pintype "passive"))
    )
    (net (code "262") (name "unconnected-(X5B-S-Pad2)") (class "Default")
      (node (ref "X5") (pin "2") (pinfunction "S_2") (pintype "passive"))
    )
    (net (code "263") (name "unconnected-(X5F-S-Pad6)") (class "Default")
      (node (ref "X5") (pin "6") (pinfunction "S_6") (pintype "passive"))
    )
  )
)
